# moire_v2_2.net
KiCad netlist of a schematic drawn in EAGLE
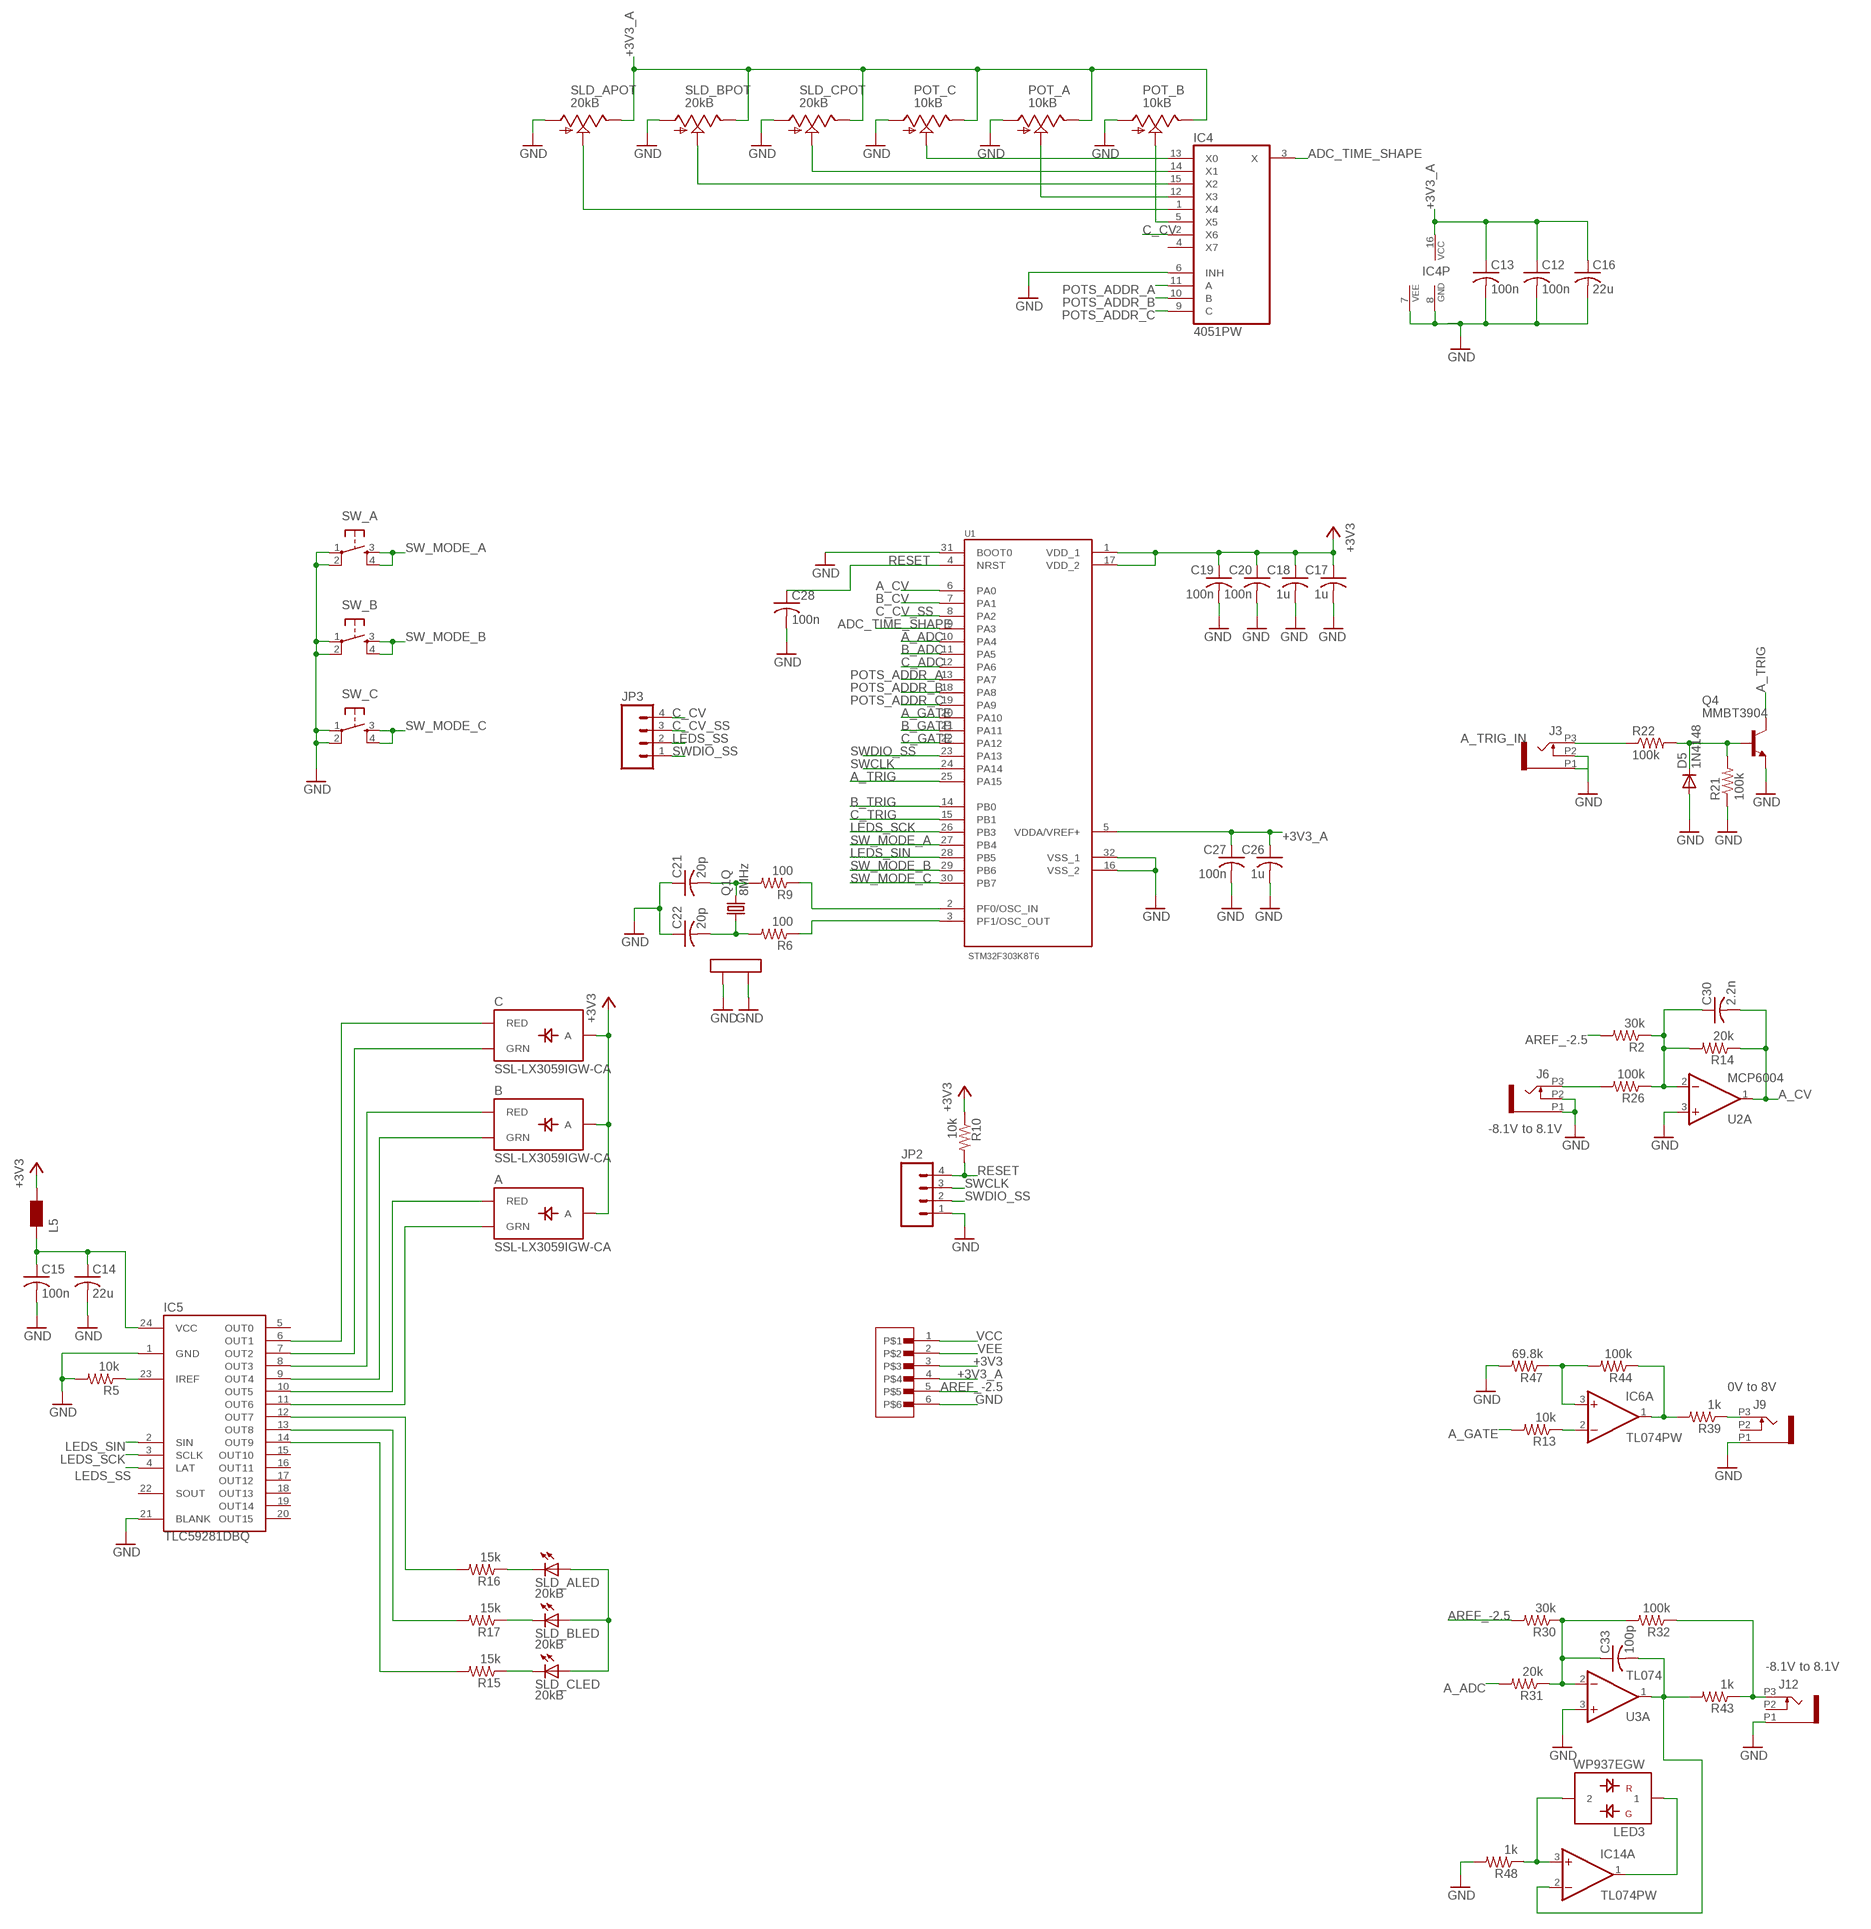
[diagram p0: schematic, sheet 1, part 1 of 2]
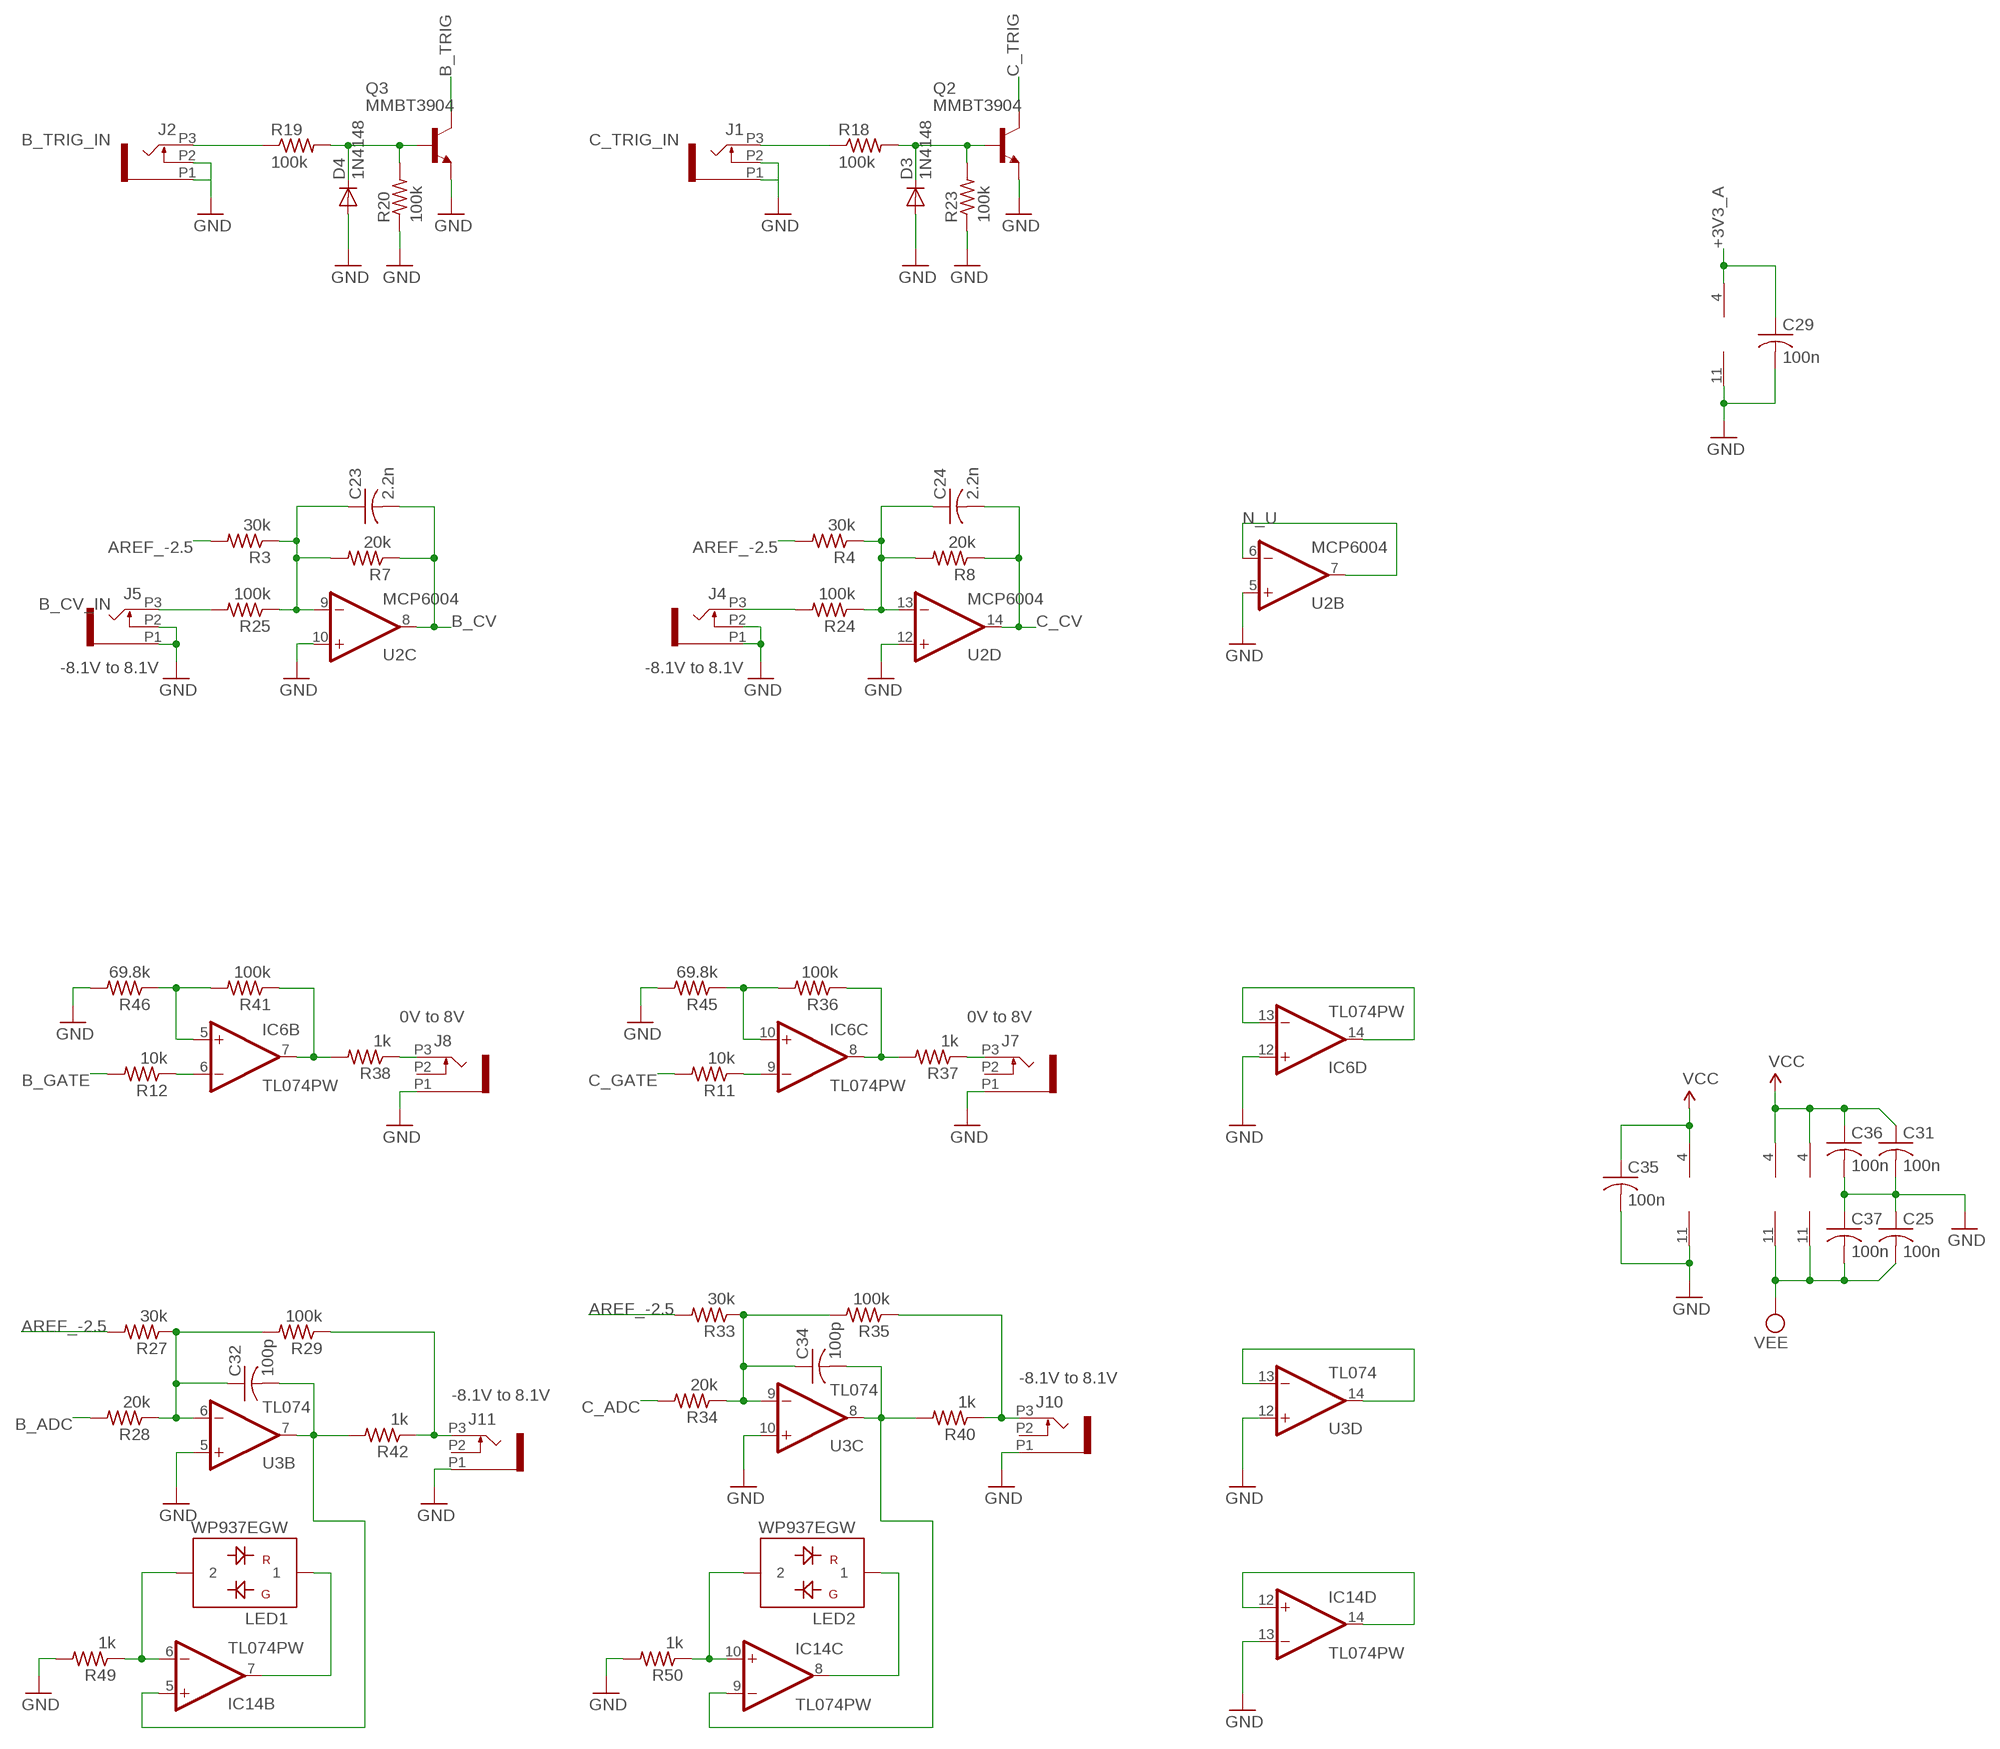
[diagram p1: schematic, sheet 1, part 2 of 2]
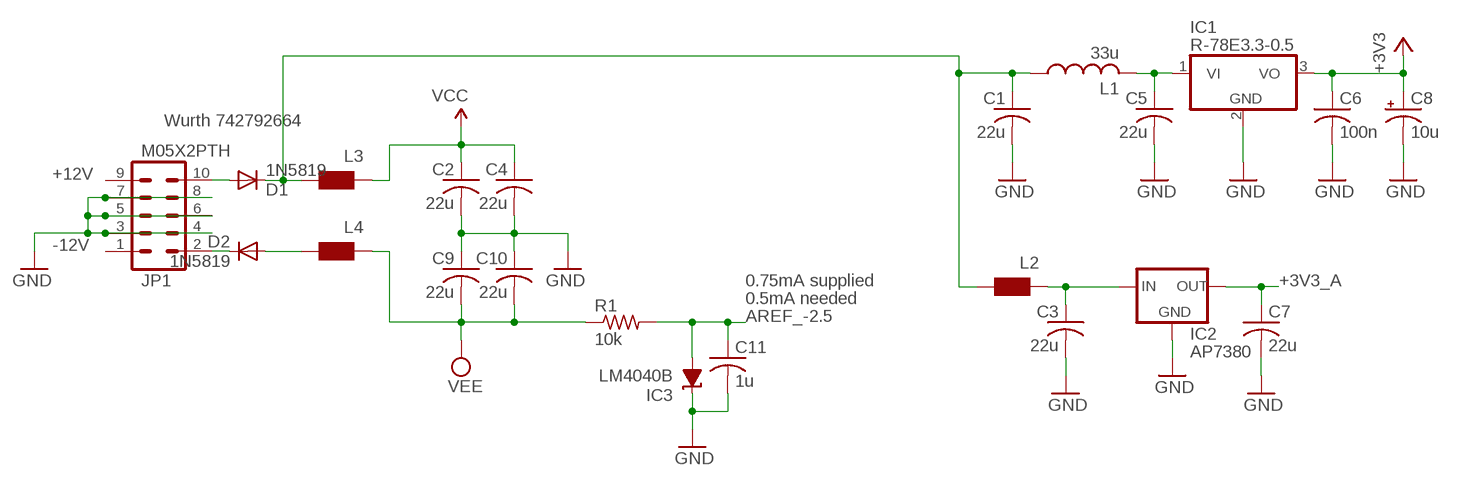
[diagram p2: schematic, sheet 2]

(export (version "E")
  (design (tool "Eeschema 10.0.6"))
  (components
    (comp (ref "A")
      (value "SSL-LX3059IGW-CA")
      (footprint "eagle-import:LED-BICOLOR-THROUGHHOLE-LUMEX")
      (libsource (lib "eagle-import") (part "LED-BICOLOR-THROUGHHOLE-CA"))
    )
    (comp (ref "B")
      (value "SSL-LX3059IGW-CA")
      (footprint "eagle-import:LED-BICOLOR-THROUGHHOLE-LUMEX")
      (libsource (lib "eagle-import") (part "LED-BICOLOR-THROUGHHOLE-CA"))
    )
    (comp (ref "C")
      (value "SSL-LX3059IGW-CA")
      (footprint "eagle-import:LED-BICOLOR-THROUGHHOLE-LUMEX")
      (libsource (lib "eagle-import") (part "LED-BICOLOR-THROUGHHOLE-CA"))
    )
    (comp (ref "C12")
      (value "100n")
      (footprint "eagle-import:RCL_C0603")
      (libsource (lib "eagle-import") (part "RCL_C-USC0603"))
    )
    (comp (ref "C13")
      (value "100n")
      (footprint "eagle-import:RCL_C0603")
      (libsource (lib "eagle-import") (part "RCL_C-USC0603"))
    )
    (comp (ref "C14")
      (value "22u")
      (footprint "eagle-import:RCL_C1206")
      (libsource (lib "eagle-import") (part "RCL_C-USC1206"))
    )
    (comp (ref "C15")
      (value "100n")
      (footprint "eagle-import:RCL_C0603")
      (libsource (lib "eagle-import") (part "RCL_C-USC0603"))
    )
    (comp (ref "C16")
      (value "22u")
      (footprint "eagle-import:RCL_C1206")
      (libsource (lib "eagle-import") (part "RCL_C-USC1206"))
    )
    (comp (ref "C17")
      (value "1u")
      (footprint "eagle-import:RCL_C0603")
      (libsource (lib "eagle-import") (part "RCL_C-USC0603"))
    )
    (comp (ref "C18")
      (value "1u")
      (footprint "eagle-import:RCL_C0603")
      (libsource (lib "eagle-import") (part "RCL_C-USC0603"))
    )
    (comp (ref "C19")
      (value "100n")
      (footprint "eagle-import:RCL_C0603")
      (libsource (lib "eagle-import") (part "RCL_C-USC0603"))
    )
    (comp (ref "C20")
      (value "100n")
      (footprint "eagle-import:RCL_C0603")
      (libsource (lib "eagle-import") (part "RCL_C-USC0603"))
    )
    (comp (ref "C21")
      (value "20p")
      (footprint "eagle-import:RCL_C0603")
      (libsource (lib "eagle-import") (part "RCL_C-USC0603"))
    )
    (comp (ref "C22")
      (value "20p")
      (footprint "eagle-import:RCL_C0603")
      (libsource (lib "eagle-import") (part "RCL_C-USC0603"))
    )
    (comp (ref "C23")
      (value "2.2n")
      (footprint "eagle-import:RCL_C0603")
      (libsource (lib "eagle-import") (part "RCL_C-USC0603"))
    )
    (comp (ref "C24")
      (value "2.2n")
      (footprint "eagle-import:RCL_C0603")
      (libsource (lib "eagle-import") (part "RCL_C-USC0603"))
    )
    (comp (ref "C25")
      (value "100n")
      (footprint "eagle-import:RCL_C0603")
      (libsource (lib "eagle-import") (part "RCL_C-USC0603"))
    )
    (comp (ref "C26")
      (value "1u")
      (footprint "eagle-import:RCL_C0603")
      (libsource (lib "eagle-import") (part "RCL_C-USC0603"))
    )
    (comp (ref "C27")
      (value "100n")
      (footprint "eagle-import:RCL_C0603")
      (libsource (lib "eagle-import") (part "RCL_C-USC0603"))
    )
    (comp (ref "C28")
      (value "100n")
      (footprint "eagle-import:RCL_C0603")
      (libsource (lib "eagle-import") (part "RCL_C-USC0603"))
    )
    (comp (ref "C29")
      (value "100n")
      (footprint "eagle-import:RCL_C0603")
      (libsource (lib "eagle-import") (part "RCL_C-USC0603"))
    )
    (comp (ref "C30")
      (value "2.2n")
      (footprint "eagle-import:RCL_C0603")
      (libsource (lib "eagle-import") (part "RCL_C-USC0603"))
    )
    (comp (ref "C31")
      (value "100n")
      (footprint "eagle-import:RCL_C0603")
      (libsource (lib "eagle-import") (part "RCL_C-USC0603"))
    )
    (comp (ref "C32")
      (value "100p")
      (footprint "eagle-import:RCL_C0603")
      (libsource (lib "eagle-import") (part "RCL_C-USC0603"))
    )
    (comp (ref "C33")
      (value "100p")
      (footprint "eagle-import:RCL_C0603")
      (libsource (lib "eagle-import") (part "RCL_C-USC0603"))
    )
    (comp (ref "C34")
      (value "100p")
      (footprint "eagle-import:RCL_C0603")
      (libsource (lib "eagle-import") (part "RCL_C-USC0603"))
    )
    (comp (ref "C35")
      (value "100n")
      (footprint "eagle-import:RCL_C0603")
      (libsource (lib "eagle-import") (part "RCL_C-USC0603"))
    )
    (comp (ref "C36")
      (value "100n")
      (footprint "eagle-import:RCL_C0603")
      (libsource (lib "eagle-import") (part "RCL_C-USC0603"))
    )
    (comp (ref "C37")
      (value "100n")
      (footprint "eagle-import:RCL_C0603")
      (libsource (lib "eagle-import") (part "RCL_C-USC0603"))
    )
    (comp (ref "D3")
      (value "1N4148")
      (footprint "eagle-import:DIODE_SOD523")
      (libsource (lib "eagle-import") (part "DIODE_DIODE-SOD523"))
    )
    (comp (ref "D4")
      (value "1N4148")
      (footprint "eagle-import:DIODE_SOD523")
      (libsource (lib "eagle-import") (part "DIODE_DIODE-SOD523"))
    )
    (comp (ref "D5")
      (value "1N4148")
      (footprint "eagle-import:DIODE_SOD523")
      (libsource (lib "eagle-import") (part "DIODE_DIODE-SOD523"))
    )
    (comp (ref "IC4")
      (value "4051PW")
      (footprint "eagle-import:TSSOP16_065")
      (libsource (lib "eagle-import") (part "4051PW"))
    )
    (comp (ref "IC5")
      (value "TLC59281DBQ")
      (footprint "eagle-import:TSSOP24_0635")
      (libsource (lib "eagle-import") (part "TLC59281DBQ"))
    )
    (comp (ref "IC6")
      (value "TL074PW")
      (footprint "eagle-import:TSSOP14_065")
      (libsource (lib "eagle-import") (part "og-linear_TL074PW"))
    )
    (comp (ref "IC14")
      (value "TL074PW")
      (footprint "eagle-import:TSSOP14_065")
      (libsource (lib "eagle-import") (part "TL074PW"))
    )
    (comp (ref "J1")
      (value "PJ301_THONKICONN6")
      (footprint "eagle-import:WQP_PJ_301M6")
      (libsource (lib "eagle-import") (part "PJ301_THONKICONN6"))
    )
    (comp (ref "J2")
      (value "PJ301_THONKICONN6")
      (footprint "eagle-import:WQP_PJ_301M6")
      (libsource (lib "eagle-import") (part "PJ301_THONKICONN6"))
    )
    (comp (ref "J3")
      (value "PJ301_THONKICONN6")
      (footprint "eagle-import:WQP_PJ_301M6")
      (libsource (lib "eagle-import") (part "PJ301_THONKICONN6"))
    )
    (comp (ref "J4")
      (value "PJ301_THONKICONN6")
      (footprint "eagle-import:WQP_PJ_301M6")
      (libsource (lib "eagle-import") (part "PJ301_THONKICONN6"))
    )
    (comp (ref "J5")
      (value "PJ301_THONKICONN6")
      (footprint "eagle-import:WQP_PJ_301M6")
      (libsource (lib "eagle-import") (part "PJ301_THONKICONN6"))
    )
    (comp (ref "J6")
      (value "PJ301_THONKICONN6")
      (footprint "eagle-import:WQP_PJ_301M6")
      (libsource (lib "eagle-import") (part "PJ301_THONKICONN6"))
    )
    (comp (ref "J7")
      (value "PJ301_THONKICONN6")
      (footprint "eagle-import:WQP_PJ_301M6")
      (libsource (lib "eagle-import") (part "PJ301_THONKICONN6"))
    )
    (comp (ref "J8")
      (value "PJ301_THONKICONN6")
      (footprint "eagle-import:WQP_PJ_301M6")
      (libsource (lib "eagle-import") (part "PJ301_THONKICONN6"))
    )
    (comp (ref "J9")
      (value "PJ301_THONKICONN6")
      (footprint "eagle-import:WQP_PJ_301M6")
      (libsource (lib "eagle-import") (part "PJ301_THONKICONN6"))
    )
    (comp (ref "J10")
      (value "PJ301_THONKICONN6")
      (footprint "eagle-import:WQP_PJ_301M6")
      (libsource (lib "eagle-import") (part "PJ301_THONKICONN6"))
    )
    (comp (ref "J11")
      (value "PJ301_THONKICONN6")
      (footprint "eagle-import:WQP_PJ_301M6")
      (libsource (lib "eagle-import") (part "PJ301_THONKICONN6"))
    )
    (comp (ref "J12")
      (value "PJ301_THONKICONN6")
      (footprint "eagle-import:WQP_PJ_301M6")
      (libsource (lib "eagle-import") (part "PJ301_THONKICONN6"))
    )
    (comp (ref "JP2")
      (value "M04PTH")
      (footprint "eagle-import:1X04")
      (libsource (lib "eagle-import") (part "M04PTH"))
    )
    (comp (ref "JP3")
      (value "M04PTH")
      (footprint "eagle-import:1X04")
      (libsource (lib "eagle-import") (part "M04PTH"))
    )
    (comp (ref "L5")
      (value "WE-CBF_0603")
      (footprint "eagle-import:0603")
      (libsource (lib "eagle-import") (part "WE-CBF_0603"))
    )
    (comp (ref "LED1")
      (value "WP937EGW")
      (footprint "eagle-import:LED3MM")
      (libsource (lib "eagle-import") (part "LED-BICOLOR-SHARED-THROUGHHOLE"))
    )
    (comp (ref "LED2")
      (value "WP937EGW")
      (footprint "eagle-import:LED3MM")
      (libsource (lib "eagle-import") (part "LED-BICOLOR-SHARED-THROUGHHOLE"))
    )
    (comp (ref "LED3")
      (value "WP937EGW")
      (footprint "eagle-import:LED3MM")
      (libsource (lib "eagle-import") (part "LED-BICOLOR-SHARED-THROUGHHOLE"))
    )
    (comp (ref "POT_A")
      (value "10kB")
      (footprint "eagle-import:ALPS_POT_VERTICAL")
      (libsource (lib "eagle-import") (part "POT_USVERTICAL"))
    )
    (comp (ref "POT_B")
      (value "10kB")
      (footprint "eagle-import:ALPS_POT_VERTICAL")
      (libsource (lib "eagle-import") (part "POT_USVERTICAL"))
    )
    (comp (ref "POT_C")
      (value "10kB")
      (footprint "eagle-import:ALPS_POT_VERTICAL")
      (libsource (lib "eagle-import") (part "POT_USVERTICAL"))
    )
    (comp (ref "Q1")
      (value "8MHz")
      (footprint "eagle-import:CTS406")
      (libsource (lib "eagle-import") (part "CRYSTAL"))
    )
    (comp (ref "Q2")
      (value "MMBT3904")
      (footprint "eagle-import:SOT23-BEC")
      (libsource (lib "eagle-import") (part "-NPN-SOT23-BECMMBT3904LT1"))
    )
    (comp (ref "Q3")
      (value "MMBT3904")
      (footprint "eagle-import:SOT23-BEC")
      (libsource (lib "eagle-import") (part "-NPN-SOT23-BECMMBT3904LT1"))
    )
    (comp (ref "Q4")
      (value "MMBT3904")
      (footprint "eagle-import:SOT23-BEC")
      (libsource (lib "eagle-import") (part "-NPN-SOT23-BECMMBT3904LT1"))
    )
    (comp (ref "R2")
      (value "30k")
      (footprint "eagle-import:RCL_R0603")
      (libsource (lib "eagle-import") (part "RCL_R-US_R0603"))
    )
    (comp (ref "R3")
      (value "30k")
      (footprint "eagle-import:RCL_R0603")
      (libsource (lib "eagle-import") (part "RCL_R-US_R0603"))
    )
    (comp (ref "R4")
      (value "30k")
      (footprint "eagle-import:RCL_R0603")
      (libsource (lib "eagle-import") (part "RCL_R-US_R0603"))
    )
    (comp (ref "R5")
      (value "10k")
      (footprint "eagle-import:RCL_R0603")
      (libsource (lib "eagle-import") (part "RCL_R-US_R0603"))
    )
    (comp (ref "R6")
      (value "100")
      (footprint "eagle-import:RCL_R0603")
      (libsource (lib "eagle-import") (part "RCL_R-US_R0603"))
    )
    (comp (ref "R7")
      (value "20k")
      (footprint "eagle-import:RCL_R0603")
      (libsource (lib "eagle-import") (part "RCL_R-US_R0603"))
    )
    (comp (ref "R8")
      (value "20k")
      (footprint "eagle-import:RCL_R0603")
      (libsource (lib "eagle-import") (part "RCL_R-US_R0603"))
    )
    (comp (ref "R9")
      (value "100")
      (footprint "eagle-import:RCL_R0603")
      (libsource (lib "eagle-import") (part "RCL_R-US_R0603"))
    )
    (comp (ref "R10")
      (value "10k")
      (footprint "eagle-import:RCL_R0603")
      (libsource (lib "eagle-import") (part "RCL_R-US_R0603"))
    )
    (comp (ref "R11")
      (value "10k")
      (footprint "eagle-import:RCL_R0603")
      (libsource (lib "eagle-import") (part "RCL_R-US_R0603"))
    )
    (comp (ref "R12")
      (value "10k")
      (footprint "eagle-import:RCL_R0603")
      (libsource (lib "eagle-import") (part "RCL_R-US_R0603"))
    )
    (comp (ref "R13")
      (value "10k")
      (footprint "eagle-import:RCL_R0603")
      (libsource (lib "eagle-import") (part "RCL_R-US_R0603"))
    )
    (comp (ref "R14")
      (value "20k")
      (footprint "eagle-import:RCL_R0603")
      (libsource (lib "eagle-import") (part "RCL_R-US_R0603"))
    )
    (comp (ref "R15")
      (value "15k")
      (footprint "eagle-import:RCL_R0603")
      (libsource (lib "eagle-import") (part "RCL_R-US_R0603"))
    )
    (comp (ref "R16")
      (value "15k")
      (footprint "eagle-import:RCL_R0603")
      (libsource (lib "eagle-import") (part "RCL_R-US_R0603"))
    )
    (comp (ref "R17")
      (value "15k")
      (footprint "eagle-import:RCL_R0603")
      (libsource (lib "eagle-import") (part "RCL_R-US_R0603"))
    )
    (comp (ref "R18")
      (value "100k")
      (footprint "eagle-import:RCL_R0603")
      (libsource (lib "eagle-import") (part "RCL_R-US_R0603"))
    )
    (comp (ref "R19")
      (value "100k")
      (footprint "eagle-import:RCL_R0603")
      (libsource (lib "eagle-import") (part "RCL_R-US_R0603"))
    )
    (comp (ref "R20")
      (value "100k")
      (footprint "eagle-import:RCL_R0603")
      (libsource (lib "eagle-import") (part "RCL_R-US_R0603"))
    )
    (comp (ref "R21")
      (value "100k")
      (footprint "eagle-import:RCL_R0603")
      (libsource (lib "eagle-import") (part "RCL_R-US_R0603"))
    )
    (comp (ref "R22")
      (value "100k")
      (footprint "eagle-import:RCL_R0603")
      (libsource (lib "eagle-import") (part "RCL_R-US_R0603"))
    )
    (comp (ref "R23")
      (value "100k")
      (footprint "eagle-import:RCL_R0603")
      (libsource (lib "eagle-import") (part "RCL_R-US_R0603"))
    )
    (comp (ref "R24")
      (value "100k")
      (footprint "eagle-import:RCL_R0603")
      (libsource (lib "eagle-import") (part "RCL_R-US_R0603"))
    )
    (comp (ref "R25")
      (value "100k")
      (footprint "eagle-import:RCL_R0603")
      (libsource (lib "eagle-import") (part "RCL_R-US_R0603"))
    )
    (comp (ref "R26")
      (value "100k")
      (footprint "eagle-import:RCL_R0603")
      (libsource (lib "eagle-import") (part "RCL_R-US_R0603"))
    )
    (comp (ref "R27")
      (value "30k")
      (footprint "eagle-import:RCL_R0603")
      (libsource (lib "eagle-import") (part "RCL_R-US_R0603"))
    )
    (comp (ref "R28")
      (value "20k")
      (footprint "eagle-import:RCL_R0603")
      (libsource (lib "eagle-import") (part "RCL_R-US_R0603"))
    )
    (comp (ref "R29")
      (value "100k")
      (footprint "eagle-import:RCL_R0603")
      (libsource (lib "eagle-import") (part "RCL_R-US_R0603"))
    )
    (comp (ref "R30")
      (value "30k")
      (footprint "eagle-import:RCL_R0603")
      (libsource (lib "eagle-import") (part "RCL_R-US_R0603"))
    )
    (comp (ref "R31")
      (value "20k")
      (footprint "eagle-import:RCL_R0603")
      (libsource (lib "eagle-import") (part "RCL_R-US_R0603"))
    )
    (comp (ref "R32")
      (value "100k")
      (footprint "eagle-import:RCL_R0603")
      (libsource (lib "eagle-import") (part "RCL_R-US_R0603"))
    )
    (comp (ref "R33")
      (value "30k")
      (footprint "eagle-import:RCL_R0603")
      (libsource (lib "eagle-import") (part "RCL_R-US_R0603"))
    )
    (comp (ref "R34")
      (value "20k")
      (footprint "eagle-import:RCL_R0603")
      (libsource (lib "eagle-import") (part "RCL_R-US_R0603"))
    )
    (comp (ref "R35")
      (value "100k")
      (footprint "eagle-import:RCL_R0603")
      (libsource (lib "eagle-import") (part "RCL_R-US_R0603"))
    )
    (comp (ref "R36")
      (value "100k")
      (footprint "eagle-import:RCL_R0603")
      (libsource (lib "eagle-import") (part "RCL_R-US_R0603"))
    )
    (comp (ref "R37")
      (value "1k")
      (footprint "eagle-import:RCL_R0603")
      (libsource (lib "eagle-import") (part "RCL_R-US_R0603"))
    )
    (comp (ref "R38")
      (value "1k")
      (footprint "eagle-import:RCL_R0603")
      (libsource (lib "eagle-import") (part "RCL_R-US_R0603"))
    )
    (comp (ref "R39")
      (value "1k")
      (footprint "eagle-import:RCL_R0603")
      (libsource (lib "eagle-import") (part "RCL_R-US_R0603"))
    )
    (comp (ref "R40")
      (value "1k")
      (footprint "eagle-import:RCL_R0603")
      (libsource (lib "eagle-import") (part "RCL_R-US_R0603"))
    )
    (comp (ref "R41")
      (value "100k")
      (footprint "eagle-import:RCL_R0603")
      (libsource (lib "eagle-import") (part "RCL_R-US_R0603"))
    )
    (comp (ref "R42")
      (value "1k")
      (footprint "eagle-import:RCL_R0603")
      (libsource (lib "eagle-import") (part "RCL_R-US_R0603"))
    )
    (comp (ref "R43")
      (value "1k")
      (footprint "eagle-import:RCL_R0603")
      (libsource (lib "eagle-import") (part "RCL_R-US_R0603"))
    )
    (comp (ref "R44")
      (value "100k")
      (footprint "eagle-import:RCL_R0603")
      (libsource (lib "eagle-import") (part "RCL_R-US_R0603"))
    )
    (comp (ref "R45")
      (value "69.8k")
      (footprint "eagle-import:RCL_R0603")
      (libsource (lib "eagle-import") (part "RCL_R-US_R0603"))
    )
    (comp (ref "R46")
      (value "69.8k")
      (footprint "eagle-import:RCL_R0603")
      (libsource (lib "eagle-import") (part "RCL_R-US_R0603"))
    )
    (comp (ref "R47")
      (value "69.8k")
      (footprint "eagle-import:RCL_R0603")
      (libsource (lib "eagle-import") (part "RCL_R-US_R0603"))
    )
    (comp (ref "R48")
      (value "1k")
      (footprint "eagle-import:RCL_R0603")
      (libsource (lib "eagle-import") (part "RCL_R-US_R0603"))
    )
    (comp (ref "R49")
      (value "1k")
      (footprint "eagle-import:RCL_R0603")
      (libsource (lib "eagle-import") (part "RCL_R-US_R0603"))
    )
    (comp (ref "R50")
      (value "1k")
      (footprint "eagle-import:RCL_R0603")
      (libsource (lib "eagle-import") (part "RCL_R-US_R0603"))
    )
    (comp (ref "SLD_A")
      (value "20kB")
      (footprint "eagle-import:BOURNS_SLIDER")
      (libsource (lib "eagle-import") (part "BOURNS_SLIDER"))
    )
    (comp (ref "SLD_B")
      (value "20kB")
      (footprint "eagle-import:BOURNS_SLIDER")
      (libsource (lib "eagle-import") (part "BOURNS_SLIDER"))
    )
    (comp (ref "SLD_C")
      (value "20kB")
      (footprint "eagle-import:BOURNS_SLIDER")
      (libsource (lib "eagle-import") (part "BOURNS_SLIDER"))
    )
    (comp (ref "SW_A")
      (value "TAC_SWITCHPTH")
      (footprint "eagle-import:TACTILE-PTH")
      (libsource (lib "eagle-import") (part "TAC_SWITCHPTH"))
    )
    (comp (ref "SW_B")
      (value "TAC_SWITCHPTH")
      (footprint "eagle-import:TACTILE-PTH")
      (libsource (lib "eagle-import") (part "TAC_SWITCHPTH"))
    )
    (comp (ref "SW_C")
      (value "TAC_SWITCHPTH")
      (footprint "eagle-import:TACTILE-PTH")
      (libsource (lib "eagle-import") (part "TAC_SWITCHPTH"))
    )
    (comp (ref "U$1")
      (value "1X6-SMD-TESTPAD")
      (footprint "eagle-import:6X1-SMD-TESTPAD")
      (libsource (lib "eagle-import") (part "1X6-SMD-TESTPAD"))
    )
    (comp (ref "U1")
      (value "STM32F303K8T6")
      (footprint "eagle-import:QFP80P900X900X160-32N")
      (fields (field (name "MF") "STMicroelectronics"))
      (libsource (lib "eagle-import") (part "STM32F303K8T6"))
    )
    (comp (ref "U2")
      (value "MCP6004")
      (footprint "eagle-import:SO14")
      (libsource (lib "eagle-import") (part "MCP6004_SMD"))
    )
    (comp (ref "U3")
      (value "TL074")
      (footprint "eagle-import:SO14")
      (libsource (lib "eagle-import") (part "TL074_SMD"))
    )
    (comp (ref "C1")
      (value "22u")
      (footprint "eagle-import:RCL_C1206")
      (libsource (lib "eagle-import") (part "RCL_C-USC1206"))
    )
    (comp (ref "C2")
      (value "22u")
      (footprint "eagle-import:RCL_C1206")
      (libsource (lib "eagle-import") (part "RCL_C-USC1206"))
    )
    (comp (ref "C3")
      (value "22u")
      (footprint "eagle-import:RCL_C1206")
      (libsource (lib "eagle-import") (part "RCL_C-USC1206"))
    )
    (comp (ref "C4")
      (value "22u")
      (footprint "eagle-import:RCL_C1206")
      (libsource (lib "eagle-import") (part "RCL_C-USC1206"))
    )
    (comp (ref "C5")
      (value "22u")
      (footprint "eagle-import:RCL_C1206")
      (libsource (lib "eagle-import") (part "RCL_C-USC1206"))
    )
    (comp (ref "C6")
      (value "100n")
      (footprint "eagle-import:RCL_C0603")
      (libsource (lib "eagle-import") (part "RCL_C-USC0603"))
    )
    (comp (ref "C7")
      (value "22u")
      (footprint "eagle-import:RCL_C1206")
      (libsource (lib "eagle-import") (part "RCL_C-USC1206"))
    )
    (comp (ref "C8")
      (value "10u")
      (footprint "eagle-import:RCL_PANASONIC_A")
      (libsource (lib "eagle-import") (part "RCL_CPOL-USA"))
    )
    (comp (ref "C9")
      (value "22u")
      (footprint "eagle-import:RCL_C1206")
      (libsource (lib "eagle-import") (part "RCL_C-USC1206"))
    )
    (comp (ref "C10")
      (value "22u")
      (footprint "eagle-import:RCL_C1206")
      (libsource (lib "eagle-import") (part "RCL_C-USC1206"))
    )
    (comp (ref "C11")
      (value "1u")
      (footprint "eagle-import:RCL_C0603")
      (libsource (lib "eagle-import") (part "RCL_C-USC0603"))
    )
    (comp (ref "D1")
      (value "1N5819")
      (footprint "eagle-import:DIODE_SOD123")
      (libsource (lib "eagle-import") (part "DIODE_DIODE-SOD123"))
    )
    (comp (ref "D2")
      (value "1N5819")
      (footprint "eagle-import:DIODE_SOD123")
      (libsource (lib "eagle-import") (part "DIODE_DIODE-SOD123"))
    )
    (comp (ref "IC1")
      (value "R-78E3.3-0.5")
      (footprint "eagle-import:WE78")
      (libsource (lib "eagle-import") (part "WE173950378"))
    )
    (comp (ref "IC2")
      (value "AP7380")
      (footprint "eagle-import:SOT89")
      (libsource (lib "eagle-import") (part "AP7380"))
    )
    (comp (ref "IC3")
      (value "LM4040B")
      (footprint "eagle-import:DBZ_R-PDSO-G3")
      (libsource (lib "eagle-import") (part "LM4041DBZB12"))
    )
    (comp (ref "JP1")
      (value "M05X2PTH")
      (footprint "eagle-import:2X5-PTH")
      (libsource (lib "eagle-import") (part "M05X2PTH"))
    )
    (comp (ref "L1")
      (value "33u")
      (footprint "eagle-import:L2012C")
      (libsource (lib "eagle-import") (part "L-USL2012C"))
    )
    (comp (ref "L2")
      (value "WE-CBF_0603")
      (footprint "eagle-import:0603")
      (libsource (lib "eagle-import") (part "WE-CBF_0603"))
    )
    (comp (ref "L3")
      (value "WE-CBF_0603")
      (footprint "eagle-import:0603")
      (libsource (lib "eagle-import") (part "WE-CBF_0603"))
    )
    (comp (ref "L4")
      (value "WE-CBF_0603")
      (footprint "eagle-import:0603")
      (libsource (lib "eagle-import") (part "WE-CBF_0603"))
    )
    (comp (ref "R1")
      (value "10k")
      (footprint "eagle-import:RCL_R0603")
      (libsource (lib "eagle-import") (part "RCL_R-US_R0603"))
    )
  )
  (nets
    (net (code "1") (name "+3V3") (class "Default")
      (node (ref "A") (pin "A") (pinfunction "A_A") (pintype "bidirectional"))
      (node (ref "B") (pin "A") (pinfunction "A_A") (pintype "bidirectional"))
      (node (ref "C") (pin "A") (pinfunction "A_A") (pintype "bidirectional"))
      (node (ref "C17") (pin "1") (pinfunction "1_1") (pintype "passive"))
      (node (ref "C18") (pin "1") (pinfunction "1_1") (pintype "passive"))
      (node (ref "C19") (pin "1") (pinfunction "1_1") (pintype "passive"))
      (node (ref "C20") (pin "1") (pinfunction "1_1") (pintype "passive"))
      (node (ref "C6") (pin "1") (pinfunction "1_1") (pintype "passive"))
      (node (ref "C8") (pin "+") (pinfunction "+_+") (pintype "passive"))
      (node (ref "IC1") (pin "3") (pinfunction "VO_3") (pintype "passive"))
      (node (ref "L5") (pin "2") (pinfunction "2_2") (pintype "passive"))
      (node (ref "R10") (pin "1") (pinfunction "1_1") (pintype "passive"))
      (node (ref "U$1") (pin "3") (pinfunction "P$3_3") (pintype "bidirectional"))
      (node (ref "U1") (pin "1") (pinfunction "VDD_1_1") (pintype "power_in"))
      (node (ref "U1") (pin "17") (pinfunction "VDD_2_17") (pintype "power_in"))
    )
    (net (code "2") (name "+3V3_A") (class "Default")
      (node (ref "C12") (pin "1") (pinfunction "1_1") (pintype "passive"))
      (node (ref "C13") (pin "1") (pinfunction "1_1") (pintype "passive"))
      (node (ref "C16") (pin "1") (pinfunction "1_1") (pintype "passive"))
      (node (ref "C26") (pin "1") (pinfunction "1_1") (pintype "passive"))
      (node (ref "C27") (pin "1") (pinfunction "1_1") (pintype "passive"))
      (node (ref "C29") (pin "1") (pinfunction "1_1") (pintype "passive"))
      (node (ref "C7") (pin "1") (pinfunction "1_1") (pintype "passive"))
      (node (ref "IC2") (pin "3") (pinfunction "OUT_3") (pintype "passive"))
      (node (ref "IC4") (pin "16") (pinfunction "VCC_16") (pintype "power_in"))
      (node (ref "POT_A") (pin "P$1") (pinfunction "E_P$1") (pintype "passive"))
      (node (ref "POT_B") (pin "P$1") (pinfunction "E_P$1") (pintype "passive"))
      (node (ref "POT_C") (pin "P$1") (pinfunction "E_P$1") (pintype "passive"))
      (node (ref "SLD_A") (pin "3") (pinfunction "E_3") (pintype "passive"))
      (node (ref "SLD_B") (pin "3") (pinfunction "E_3") (pintype "passive"))
      (node (ref "SLD_C") (pin "3") (pinfunction "E_3") (pintype "passive"))
      (node (ref "U$1") (pin "4") (pinfunction "P$4_4") (pintype "bidirectional"))
      (node (ref "U1") (pin "5") (pinfunction "VDDA/VREF+_5") (pintype "power_in"))
      (node (ref "U2") (pin "4") (pinfunction "V+_4") (pintype "power_in"))
    )
    (net (code "3") (name "+12V") (class "Default")
      (node (ref "D1") (pin "A") (pinfunction "A_A") (pintype "passive"))
      (node (ref "JP1") (pin "10") (pinfunction "10_10") (pintype "passive"))
      (node (ref "JP1") (pin "9") (pinfunction "9_9") (pintype "passive"))
    )
    (net (code "4") (name "-12V") (class "Default")
      (node (ref "D2") (pin "C") (pinfunction "C_C") (pintype "passive"))
      (node (ref "JP1") (pin "1") (pinfunction "1_1") (pintype "passive"))
      (node (ref "JP1") (pin "2") (pinfunction "2_2") (pintype "passive"))
    )
    (net (code "5") (name "ADC_TIME_SHAPE") (class "Default")
      (node (ref "IC4") (pin "3") (pinfunction "X_3") (pintype "bidirectional"))
      (node (ref "U1") (pin "9") (pinfunction "PA3_9") (pintype "bidirectional"))
    )
    (net (code "6") (name "AREF_-2.5") (class "Default")
      (node (ref "C11") (pin "1") (pinfunction "1_1") (pintype "passive"))
      (node (ref "IC3") (pin "2") (pinfunction "A_2") (pintype "passive"))
      (node (ref "R1") (pin "2") (pinfunction "2_2") (pintype "passive"))
      (node (ref "R2") (pin "2") (pinfunction "2_2") (pintype "passive"))
      (node (ref "R27") (pin "2") (pinfunction "2_2") (pintype "passive"))
      (node (ref "R3") (pin "2") (pinfunction "2_2") (pintype "passive"))
      (node (ref "R30") (pin "2") (pinfunction "2_2") (pintype "passive"))
      (node (ref "R33") (pin "2") (pinfunction "2_2") (pintype "passive"))
      (node (ref "R4") (pin "2") (pinfunction "2_2") (pintype "passive"))
      (node (ref "U$1") (pin "5") (pinfunction "P$5_5") (pintype "bidirectional"))
    )
    (net (code "7") (name "A_ADC") (class "Default")
      (node (ref "R31") (pin "2") (pinfunction "2_2") (pintype "passive"))
      (node (ref "U1") (pin "10") (pinfunction "PA4_10") (pintype "bidirectional"))
    )
    (net (code "8") (name "A_CV") (class "Default")
      (node (ref "C30") (pin "2") (pinfunction "2_2") (pintype "passive"))
      (node (ref "R14") (pin "1") (pinfunction "1_1") (pintype "passive"))
      (node (ref "U1") (pin "6") (pinfunction "PA0_6") (pintype "bidirectional"))
      (node (ref "U2") (pin "1") (pinfunction "OUT_1") (pintype "output"))
    )
    (net (code "9") (name "A_GATE") (class "Default")
      (node (ref "R13") (pin "2") (pinfunction "2_2") (pintype "passive"))
      (node (ref "U1") (pin "20") (pinfunction "PA10_20") (pintype "bidirectional"))
    )
    (net (code "10") (name "A_TRIG") (class "Default")
      (node (ref "Q4") (pin "C") (pinfunction "C_C") (pintype "passive"))
      (node (ref "U1") (pin "25") (pinfunction "PA15_25") (pintype "bidirectional"))
    )
    (net (code "11") (name "A_TRIG_IN") (class "Default")
      (node (ref "J3") (pin "P3") (pinfunction "3_P3") (pintype "passive"))
      (node (ref "R22") (pin "1") (pinfunction "1_1") (pintype "passive"))
    )
    (net (code "12") (name "B_ADC") (class "Default")
      (node (ref "R28") (pin "2") (pinfunction "2_2") (pintype "passive"))
      (node (ref "U1") (pin "11") (pinfunction "PA5_11") (pintype "bidirectional"))
    )
    (net (code "13") (name "B_CV") (class "Default")
      (node (ref "C23") (pin "2") (pinfunction "2_2") (pintype "passive"))
      (node (ref "R7") (pin "1") (pinfunction "1_1") (pintype "passive"))
      (node (ref "U1") (pin "7") (pinfunction "PA1_7") (pintype "bidirectional"))
      (node (ref "U2") (pin "8") (pinfunction "OUT_8") (pintype "output"))
    )
    (net (code "14") (name "B_CV_IN") (class "Default")
      (node (ref "J5") (pin "P3") (pinfunction "3_P3") (pintype "passive"))
      (node (ref "R25") (pin "2") (pinfunction "2_2") (pintype "passive"))
    )
    (net (code "15") (name "B_GATE") (class "Default")
      (node (ref "R12") (pin "2") (pinfunction "2_2") (pintype "passive"))
      (node (ref "U1") (pin "21") (pinfunction "PA11_21") (pintype "bidirectional"))
    )
    (net (code "16") (name "B_TRIG") (class "Default")
      (node (ref "Q3") (pin "C") (pinfunction "C_C") (pintype "passive"))
      (node (ref "U1") (pin "14") (pinfunction "PB0_14") (pintype "bidirectional"))
    )
    (net (code "17") (name "B_TRIG_IN") (class "Default")
      (node (ref "J2") (pin "P3") (pinfunction "3_P3") (pintype "passive"))
      (node (ref "R19") (pin "1") (pinfunction "1_1") (pintype "passive"))
    )
    (net (code "18") (name "C_ADC") (class "Default")
      (node (ref "R34") (pin "2") (pinfunction "2_2") (pintype "passive"))
      (node (ref "U1") (pin "12") (pinfunction "PA6_12") (pintype "bidirectional"))
    )
    (net (code "19") (name "C_CV") (class "Default")
      (node (ref "C24") (pin "2") (pinfunction "2_2") (pintype "passive"))
      (node (ref "IC4") (pin "2") (pinfunction "X6_2") (pintype "bidirectional"))
      (node (ref "JP3") (pin "4") (pinfunction "4_4") (pintype "passive"))
      (node (ref "R8") (pin "1") (pinfunction "1_1") (pintype "passive"))
      (node (ref "U2") (pin "14") (pinfunction "OUT_14") (pintype "output"))
    )
    (net (code "20") (name "C_CV_SS") (class "Default")
      (node (ref "JP3") (pin "3") (pinfunction "3_3") (pintype "passive"))
      (node (ref "U1") (pin "8") (pinfunction "PA2_8") (pintype "bidirectional"))
    )
    (net (code "21") (name "C_GATE") (class "Default")
      (node (ref "R11") (pin "2") (pinfunction "2_2") (pintype "passive"))
      (node (ref "U1") (pin "22") (pinfunction "PA12_22") (pintype "bidirectional"))
    )
    (net (code "22") (name "C_TRIG") (class "Default")
      (node (ref "Q2") (pin "C") (pinfunction "C_C") (pintype "passive"))
      (node (ref "U1") (pin "15") (pinfunction "PB1_15") (pintype "bidirectional"))
    )
    (net (code "23") (name "C_TRIG_IN") (class "Default")
      (node (ref "J1") (pin "P3") (pinfunction "3_P3") (pintype "passive"))
      (node (ref "R18") (pin "1") (pinfunction "1_1") (pintype "passive"))
    )
    (net (code "24") (name "GND") (class "Default")
      (node (ref "C1") (pin "2") (pinfunction "2_2") (pintype "passive"))
      (node (ref "C10") (pin "1") (pinfunction "1_1") (pintype "passive"))
      (node (ref "C11") (pin "2") (pinfunction "2_2") (pintype "passive"))
      (node (ref "C12") (pin "2") (pinfunction "2_2") (pintype "passive"))
      (node (ref "C13") (pin "2") (pinfunction "2_2") (pintype "passive"))
      (node (ref "C14") (pin "2") (pinfunction "2_2") (pintype "passive"))
      (node (ref "C15") (pin "2") (pinfunction "2_2") (pintype "passive"))
      (node (ref "C16") (pin "2") (pinfunction "2_2") (pintype "passive"))
      (node (ref "C17") (pin "2") (pinfunction "2_2") (pintype "passive"))
      (node (ref "C18") (pin "2") (pinfunction "2_2") (pintype "passive"))
      (node (ref "C19") (pin "2") (pinfunction "2_2") (pintype "passive"))
      (node (ref "C2") (pin "2") (pinfunction "2_2") (pintype "passive"))
      (node (ref "C20") (pin "2") (pinfunction "2_2") (pintype "passive"))
      (node (ref "C21") (pin "1") (pinfunction "1_1") (pintype "passive"))
      (node (ref "C22") (pin "1") (pinfunction "1_1") (pintype "passive"))
      (node (ref "C25") (pin "1") (pinfunction "1_1") (pintype "passive"))
      (node (ref "C26") (pin "2") (pinfunction "2_2") (pintype "passive"))
      (node (ref "C27") (pin "2") (pinfunction "2_2") (pintype "passive"))
      (node (ref "C28") (pin "2") (pinfunction "2_2") (pintype "passive"))
      (node (ref "C29") (pin "2") (pinfunction "2_2") (pintype "passive"))
      (node (ref "C3") (pin "2") (pinfunction "2_2") (pintype "passive"))
      (node (ref "C31") (pin "2") (pinfunction "2_2") (pintype "passive"))
      (node (ref "C35") (pin "2") (pinfunction "2_2") (pintype "passive"))
      (node (ref "C36") (pin "2") (pinfunction "2_2") (pintype "passive"))
      (node (ref "C37") (pin "1") (pinfunction "1_1") (pintype "passive"))
      (node (ref "C4") (pin "2") (pinfunction "2_2") (pintype "passive"))
      (node (ref "C5") (pin "2") (pinfunction "2_2") (pintype "passive"))
      (node (ref "C6") (pin "2") (pinfunction "2_2") (pintype "passive"))
      (node (ref "C7") (pin "2") (pinfunction "2_2") (pintype "passive"))
      (node (ref "C8") (pin "-") (pinfunction "-_-") (pintype "passive"))
      (node (ref "C9") (pin "1") (pinfunction "1_1") (pintype "passive"))
      (node (ref "D3") (pin "A") (pinfunction "A_A") (pintype "passive"))
      (node (ref "D4") (pin "A") (pinfunction "A_A") (pintype "passive"))
      (node (ref "D5") (pin "A") (pinfunction "A_A") (pintype "passive"))
      (node (ref "IC1") (pin "2") (pinfunction "GND_2") (pintype "passive"))
      (node (ref "IC14") (pin "13") (pinfunction "-IN_13") (pintype "input"))
      (node (ref "IC2") (pin "1") (pinfunction "GND_1") (pintype "input"))
      (node (ref "IC3") (pin "1") (pinfunction "C_1") (pintype "passive"))
      (node (ref "IC4") (pin "6") (pinfunction "INH_6") (pintype "input"))
      (node (ref "IC4") (pin "7") (pinfunction "VEE_7") (pintype "power_in"))
      (node (ref "IC4") (pin "8") (pinfunction "GND_8") (pintype "power_in"))
      (node (ref "IC5") (pin "1") (pinfunction "GND_1") (pintype "bidirectional"))
      (node (ref "IC5") (pin "21") (pinfunction "BLANK_21") (pintype "bidirectional"))
      (node (ref "IC6") (pin "11") (pinfunction "V-_11") (pintype "power_in"))
      (node (ref "IC6") (pin "12") (pinfunction "+IN_12") (pintype "input"))
      (node (ref "J1") (pin "P1") (pinfunction "1_P1") (pintype "passive"))
      (node (ref "J1") (pin "P2") (pinfunction "2_P2") (pintype "passive"))
      (node (ref "J10") (pin "P1") (pinfunction "1_P1") (pintype "passive"))
      (node (ref "J11") (pin "P1") (pinfunction "1_P1") (pintype "passive"))
      (node (ref "J12") (pin "P1") (pinfunction "1_P1") (pintype "passive"))
      (node (ref "J2") (pin "P1") (pinfunction "1_P1") (pintype "passive"))
      (node (ref "J2") (pin "P2") (pinfunction "2_P2") (pintype "passive"))
      (node (ref "J3") (pin "P1") (pinfunction "1_P1") (pintype "passive"))
      (node (ref "J3") (pin "P2") (pinfunction "2_P2") (pintype "passive"))
      (node (ref "J4") (pin "P1") (pinfunction "1_P1") (pintype "passive"))
      (node (ref "J4") (pin "P2") (pinfunction "2_P2") (pintype "passive"))
      (node (ref "J5") (pin "P1") (pinfunction "1_P1") (pintype "passive"))
      (node (ref "J5") (pin "P2") (pinfunction "2_P2") (pintype "passive"))
      (node (ref "J6") (pin "P1") (pinfunction "1_P1") (pintype "passive"))
      (node (ref "J6") (pin "P2") (pinfunction "2_P2") (pintype "passive"))
      (node (ref "J7") (pin "P1") (pinfunction "1_P1") (pintype "passive"))
      (node (ref "J8") (pin "P1") (pinfunction "1_P1") (pintype "passive"))
      (node (ref "J9") (pin "P1") (pinfunction "1_P1") (pintype "passive"))
      (node (ref "JP1") (pin "3") (pinfunction "3_3") (pintype "passive"))
      (node (ref "JP1") (pin "4") (pinfunction "4_4") (pintype "passive"))
      (node (ref "JP1") (pin "5") (pinfunction "5_5") (pintype "passive"))
      (node (ref "JP1") (pin "6") (pinfunction "6_6") (pintype "passive"))
      (node (ref "JP1") (pin "7") (pinfunction "7_7") (pintype "passive"))
      (node (ref "JP1") (pin "8") (pinfunction "8_8") (pintype "passive"))
      (node (ref "JP2") (pin "1") (pinfunction "1_1") (pintype "passive"))
      (node (ref "POT_A") (pin "P$3") (pinfunction "A_P$3") (pintype "passive"))
      (node (ref "POT_B") (pin "P$3") (pinfunction "A_P$3") (pintype "passive"))
      (node (ref "POT_C") (pin "P$3") (pinfunction "A_P$3") (pintype "passive"))
      (node (ref "Q1") (pin "2") (pinfunction "LID1_2") (pintype "power_in"))
      (node (ref "Q1") (pin "4") (pinfunction "LID2_4") (pintype "power_in"))
      (node (ref "Q2") (pin "E") (pinfunction "E_E") (pintype "passive"))
      (node (ref "Q3") (pin "E") (pinfunction "E_E") (pintype "passive"))
      (node (ref "Q4") (pin "E") (pinfunction "E_E") (pintype "passive"))
      (node (ref "R20") (pin "1") (pinfunction "1_1") (pintype "passive"))
      (node (ref "R21") (pin "1") (pinfunction "1_1") (pintype "passive"))
      (node (ref "R23") (pin "1") (pinfunction "1_1") (pintype "passive"))
      (node (ref "R45") (pin "2") (pinfunction "2_2") (pintype "passive"))
      (node (ref "R46") (pin "2") (pinfunction "2_2") (pintype "passive"))
      (node (ref "R47") (pin "2") (pinfunction "2_2") (pintype "passive"))
      (node (ref "R48") (pin "2") (pinfunction "2_2") (pintype "passive"))
      (node (ref "R49") (pin "2") (pinfunction "2_2") (pintype "passive"))
      (node (ref "R5") (pin "2") (pinfunction "2_2") (pintype "passive"))
      (node (ref "R50") (pin "2") (pinfunction "2_2") (pintype "passive"))
      (node (ref "SLD_A") (pin "1") (pinfunction "A_1") (pintype "passive"))
      (node (ref "SLD_B") (pin "1") (pinfunction "A_1") (pintype "passive"))
      (node (ref "SLD_C") (pin "1") (pinfunction "A_1") (pintype "passive"))
      (node (ref "SW_A") (pin "1") (pinfunction "1_1") (pintype "passive"))
      (node (ref "SW_A") (pin "2") (pinfunction "2_2") (pintype "passive"))
      (node (ref "SW_B") (pin "1") (pinfunction "1_1") (pintype "passive"))
      (node (ref "SW_B") (pin "2") (pinfunction "2_2") (pintype "passive"))
      (node (ref "SW_C") (pin "1") (pinfunction "1_1") (pintype "passive"))
      (node (ref "SW_C") (pin "2") (pinfunction "2_2") (pintype "passive"))
      (node (ref "U$1") (pin "6") (pinfunction "P$6_6") (pintype "bidirectional"))
      (node (ref "U1") (pin "16") (pinfunction "VSS_2_16") (pintype "power_in"))
      (node (ref "U1") (pin "31") (pinfunction "BOOT0_31") (pintype "input"))
      (node (ref "U1") (pin "32") (pinfunction "VSS_1_32") (pintype "power_in"))
      (node (ref "U2") (pin "10") (pinfunction "+IN_10") (pintype "input"))
      (node (ref "U2") (pin "11") (pinfunction "V-_11") (pintype "power_in"))
      (node (ref "U2") (pin "12") (pinfunction "+IN_12") (pintype "input"))
      (node (ref "U2") (pin "3") (pinfunction "+IN_3") (pintype "input"))
      (node (ref "U2") (pin "5") (pinfunction "+IN_5") (pintype "input"))
      (node (ref "U3") (pin "10") (pinfunction "+IN_10") (pintype "input"))
      (node (ref "U3") (pin "12") (pinfunction "+IN_12") (pintype "input"))
      (node (ref "U3") (pin "3") (pinfunction "+IN_3") (pintype "input"))
      (node (ref "U3") (pin "5") (pinfunction "+IN_5") (pintype "input"))
    )
    (net (code "25") (name "LEDS_SCK") (class "Default")
      (node (ref "IC5") (pin "3") (pinfunction "SCLK_3") (pintype "bidirectional"))
      (node (ref "U1") (pin "26") (pinfunction "PB3_26") (pintype "bidirectional"))
    )
    (net (code "26") (name "LEDS_SIN") (class "Default")
      (node (ref "IC5") (pin "2") (pinfunction "SIN_2") (pintype "bidirectional"))
      (node (ref "U1") (pin "28") (pinfunction "PB5_28") (pintype "bidirectional"))
    )
    (net (code "27") (name "LEDS_SS") (class "Default")
      (node (ref "IC5") (pin "4") (pinfunction "LAT_4") (pintype "bidirectional"))
      (node (ref "JP3") (pin "2") (pinfunction "2_2") (pintype "passive"))
    )
    (net (code "28") (name "N_U") (class "Default")
      (node (ref "U2") (pin "6") (pinfunction "-IN_6") (pintype "input"))
      (node (ref "U2") (pin "7") (pinfunction "OUT_7") (pintype "output"))
    )
    (net (code "29") (name "Net-(A-GRN)") (class "Default")
      (node (ref "A") (pin "GREEN_C") (pinfunction "GRN_GREEN_C") (pintype "bidirectional"))
      (node (ref "IC5") (pin "11") (pinfunction "OUT6_11") (pintype "bidirectional"))
    )
    (net (code "30") (name "Net-(A-RED)") (class "Default")
      (node (ref "A") (pin "RED_C") (pinfunction "RED_RED_C") (pintype "bidirectional"))
      (node (ref "IC5") (pin "10") (pinfunction "OUT5_10") (pintype "bidirectional"))
    )
    (net (code "31") (name "Net-(B-GRN)") (class "Default")
      (node (ref "B") (pin "GREEN_C") (pinfunction "GRN_GREEN_C") (pintype "bidirectional"))
      (node (ref "IC5") (pin "9") (pinfunction "OUT4_9") (pintype "bidirectional"))
    )
    (net (code "32") (name "Net-(B-RED)") (class "Default")
      (node (ref "B") (pin "RED_C") (pinfunction "RED_RED_C") (pintype "bidirectional"))
      (node (ref "IC5") (pin "8") (pinfunction "OUT3_8") (pintype "bidirectional"))
    )
    (net (code "33") (name "Net-(C-GRN)") (class "Default")
      (node (ref "C") (pin "GREEN_C") (pinfunction "GRN_GREEN_C") (pintype "bidirectional"))
      (node (ref "IC5") (pin "7") (pinfunction "OUT2_7") (pintype "bidirectional"))
    )
    (net (code "34") (name "Net-(C-RED)") (class "Default")
      (node (ref "C") (pin "RED_C") (pinfunction "RED_RED_C") (pintype "bidirectional"))
      (node (ref "IC5") (pin "6") (pinfunction "OUT1_6") (pintype "bidirectional"))
    )
    (net (code "35") (name "Net-(C1-Pad1)") (class "Default")
      (node (ref "C1") (pin "1") (pinfunction "1_1") (pintype "passive"))
      (node (ref "D1") (pin "C") (pinfunction "C_C") (pintype "passive"))
      (node (ref "L1") (pin "1") (pinfunction "1_1") (pintype "passive"))
      (node (ref "L2") (pin "2") (pinfunction "2_2") (pintype "passive"))
      (node (ref "L3") (pin "2") (pinfunction "2_2") (pintype "passive"))
    )
    (net (code "36") (name "Net-(C3-Pad1)") (class "Default")
      (node (ref "C3") (pin "1") (pinfunction "1_1") (pintype "passive"))
      (node (ref "IC2") (pin "2") (pinfunction "IN_2") (pintype "input"))
      (node (ref "IC2") (pin "4") (pinfunction "IN_4") (pintype "input"))
      (node (ref "L2") (pin "1") (pinfunction "1_1") (pintype "passive"))
    )
    (net (code "37") (name "Net-(C22-Pad2)") (class "Default")
      (node (ref "C22") (pin "2") (pinfunction "2_2") (pintype "passive"))
      (node (ref "Q1") (pin "1") (pinfunction "1_1") (pintype "passive"))
      (node (ref "R6") (pin "2") (pinfunction "2_2") (pintype "passive"))
    )
    (net (code "38") (name "Net-(D2-PadA)") (class "Default")
      (node (ref "D2") (pin "A") (pinfunction "A_A") (pintype "passive"))
      (node (ref "L4") (pin "2") (pinfunction "2_2") (pintype "passive"))
    )
    (net (code "39") (name "Net-(D3-PadC)") (class "Default")
      (node (ref "D3") (pin "C") (pinfunction "C_C") (pintype "passive"))
      (node (ref "Q2") (pin "B") (pinfunction "B_B") (pintype "passive"))
      (node (ref "R18") (pin "2") (pinfunction "2_2") (pintype "passive"))
      (node (ref "R23") (pin "2") (pinfunction "2_2") (pintype "passive"))
    )
    (net (code "40") (name "Net-(D4-PadC)") (class "Default")
      (node (ref "D4") (pin "C") (pinfunction "C_C") (pintype "passive"))
      (node (ref "Q3") (pin "B") (pinfunction "B_B") (pintype "passive"))
      (node (ref "R19") (pin "2") (pinfunction "2_2") (pintype "passive"))
      (node (ref "R20") (pin "2") (pinfunction "2_2") (pintype "passive"))
    )
    (net (code "41") (name "Net-(D5-PadC)") (class "Default")
      (node (ref "D5") (pin "C") (pinfunction "C_C") (pintype "passive"))
      (node (ref "Q4") (pin "B") (pinfunction "B_B") (pintype "passive"))
      (node (ref "R21") (pin "2") (pinfunction "2_2") (pintype "passive"))
      (node (ref "R22") (pin "2") (pinfunction "2_2") (pintype "passive"))
    )
    (net (code "42") (name "Net-(IC1-VI)") (class "Default")
      (node (ref "C5") (pin "1") (pinfunction "1_1") (pintype "passive"))
      (node (ref "IC1") (pin "1") (pinfunction "VI_1") (pintype "input"))
      (node (ref "L1") (pin "2") (pinfunction "2_2") (pintype "passive"))
    )
    (net (code "43") (name "Net-(IC4A-X0)") (class "Default")
      (node (ref "IC4") (pin "13") (pinfunction "X0_13") (pintype "bidirectional"))
      (node (ref "POT_C") (pin "P$2") (pinfunction "S_P$2") (pintype "passive"))
    )
    (net (code "44") (name "Net-(IC4A-X1)") (class "Default")
      (node (ref "IC4") (pin "14") (pinfunction "X1_14") (pintype "bidirectional"))
      (node (ref "SLD_C") (pin "2") (pinfunction "S_2") (pintype "passive"))
    )
    (net (code "45") (name "Net-(IC4A-X2)") (class "Default")
      (node (ref "IC4") (pin "15") (pinfunction "X2_15") (pintype "bidirectional"))
      (node (ref "SLD_B") (pin "2") (pinfunction "S_2") (pintype "passive"))
    )
    (net (code "46") (name "Net-(IC4A-X3)") (class "Default")
      (node (ref "IC4") (pin "12") (pinfunction "X3_12") (pintype "bidirectional"))
      (node (ref "POT_A") (pin "P$2") (pinfunction "S_P$2") (pintype "passive"))
    )
    (net (code "47") (name "Net-(IC4A-X4)") (class "Default")
      (node (ref "IC4") (pin "1") (pinfunction "X4_1") (pintype "bidirectional"))
      (node (ref "SLD_A") (pin "2") (pinfunction "S_2") (pintype "passive"))
    )
    (net (code "48") (name "Net-(IC4A-X5)") (class "Default")
      (node (ref "IC4") (pin "5") (pinfunction "X5_5") (pintype "bidirectional"))
      (node (ref "POT_B") (pin "P$2") (pinfunction "S_P$2") (pintype "passive"))
    )
    (net (code "49") (name "Net-(IC5-IREF)") (class "Default")
      (node (ref "IC5") (pin "23") (pinfunction "IREF_23") (pintype "bidirectional"))
      (node (ref "R5") (pin "1") (pinfunction "1_1") (pintype "passive"))
    )
    (net (code "50") (name "Net-(IC5-OUT7)") (class "Default")
      (node (ref "IC5") (pin "12") (pinfunction "OUT7_12") (pintype "bidirectional"))
      (node (ref "R16") (pin "2") (pinfunction "2_2") (pintype "passive"))
    )
    (net (code "51") (name "Net-(IC5-OUT8)") (class "Default")
      (node (ref "IC5") (pin "13") (pinfunction "OUT8_13") (pintype "bidirectional"))
      (node (ref "R17") (pin "2") (pinfunction "2_2") (pintype "passive"))
    )
    (net (code "52") (name "Net-(IC5-OUT9)") (class "Default")
      (node (ref "IC5") (pin "14") (pinfunction "OUT9_14") (pintype "bidirectional"))
      (node (ref "R15") (pin "2") (pinfunction "2_2") (pintype "passive"))
    )
    (net (code "53") (name "Net-(IC5-VCC)") (class "Default")
      (node (ref "C14") (pin "1") (pinfunction "1_1") (pintype "passive"))
      (node (ref "C15") (pin "1") (pinfunction "1_1") (pintype "passive"))
      (node (ref "IC5") (pin "24") (pinfunction "VCC_24") (pintype "bidirectional"))
      (node (ref "L5") (pin "1") (pinfunction "1_1") (pintype "passive"))
    )
    (net (code "54") (name "Net-(IC6A-+IN)") (class "Default")
      (node (ref "IC6") (pin "3") (pinfunction "+IN_3") (pintype "input"))
      (node (ref "R44") (pin "2") (pinfunction "2_2") (pintype "passive"))
      (node (ref "R47") (pin "1") (pinfunction "1_1") (pintype "passive"))
    )
    (net (code "55") (name "Net-(IC6A--IN)") (class "Default")
      (node (ref "IC6") (pin "2") (pinfunction "-IN_2") (pintype "input"))
      (node (ref "R13") (pin "1") (pinfunction "1_1") (pintype "passive"))
    )
    (net (code "56") (name "Net-(IC6A-OUT)") (class "Default")
      (node (ref "IC6") (pin "1") (pinfunction "OUT_1") (pintype "output"))
      (node (ref "R39") (pin "2") (pinfunction "2_2") (pintype "passive"))
      (node (ref "R44") (pin "1") (pinfunction "1_1") (pintype "passive"))
    )
    (net (code "57") (name "Net-(IC6B-+IN)") (class "Default")
      (node (ref "IC6") (pin "5") (pinfunction "+IN_5") (pintype "input"))
      (node (ref "R41") (pin "2") (pinfunction "2_2") (pintype "passive"))
      (node (ref "R46") (pin "1") (pinfunction "1_1") (pintype "passive"))
    )
    (net (code "58") (name "Net-(IC6B--IN)") (class "Default")
      (node (ref "IC6") (pin "6") (pinfunction "-IN_6") (pintype "input"))
      (node (ref "R12") (pin "1") (pinfunction "1_1") (pintype "passive"))
    )
    (net (code "59") (name "Net-(IC6B-OUT)") (class "Default")
      (node (ref "IC6") (pin "7") (pinfunction "OUT_7") (pintype "output"))
      (node (ref "R38") (pin "2") (pinfunction "2_2") (pintype "passive"))
      (node (ref "R41") (pin "1") (pinfunction "1_1") (pintype "passive"))
    )
    (net (code "60") (name "Net-(IC6C-+IN)") (class "Default")
      (node (ref "IC6") (pin "10") (pinfunction "+IN_10") (pintype "input"))
      (node (ref "R36") (pin "2") (pinfunction "2_2") (pintype "passive"))
      (node (ref "R45") (pin "1") (pinfunction "1_1") (pintype "passive"))
    )
    (net (code "61") (name "Net-(IC6C--IN)") (class "Default")
      (node (ref "IC6") (pin "9") (pinfunction "-IN_9") (pintype "input"))
      (node (ref "R11") (pin "1") (pinfunction "1_1") (pintype "passive"))
    )
    (net (code "62") (name "Net-(IC6C-OUT)") (class "Default")
      (node (ref "IC6") (pin "8") (pinfunction "OUT_8") (pintype "output"))
      (node (ref "R36") (pin "1") (pinfunction "1_1") (pintype "passive"))
      (node (ref "R37") (pin "2") (pinfunction "2_2") (pintype "passive"))
    )
    (net (code "63") (name "Net-(IC6D--IN)") (class "Default")
      (node (ref "IC6") (pin "13") (pinfunction "-IN_13") (pintype "input"))
      (node (ref "IC6") (pin "14") (pinfunction "OUT_14") (pintype "output"))
    )
    (net (code "64") (name "Net-(IC14A-+IN)") (class "Default")
      (node (ref "IC14") (pin "3") (pinfunction "+IN_3") (pintype "input"))
      (node (ref "LED3") (pin "2") (pinfunction "2_2") (pintype "bidirectional"))
      (node (ref "R48") (pin "1") (pinfunction "1_1") (pintype "passive"))
    )
    (net (code "65") (name "Net-(IC14A--IN)") (class "Default")
      (node (ref "C33") (pin "2") (pinfunction "2_2") (pintype "passive"))
      (node (ref "IC14") (pin "2") (pinfunction "-IN_2") (pintype "input"))
      (node (ref "R43") (pin "2") (pinfunction "2_2") (pintype "passive"))
      (node (ref "U3") (pin "1") (pinfunction "OUT_1") (pintype "output"))
    )
    (net (code "66") (name "Net-(IC14A-OUT)") (class "Default")
      (node (ref "IC14") (pin "1") (pinfunction "OUT_1") (pintype "output"))
      (node (ref "LED3") (pin "1") (pinfunction "1_1") (pintype "bidirectional"))
    )
    (net (code "67") (name "Net-(IC14B-+IN)") (class "Default")
      (node (ref "C32") (pin "2") (pinfunction "2_2") (pintype "passive"))
      (node (ref "IC14") (pin "5") (pinfunction "+IN_5") (pintype "input"))
      (node (ref "R42") (pin "2") (pinfunction "2_2") (pintype "passive"))
      (node (ref "U3") (pin "7") (pinfunction "OUT_7") (pintype "output"))
    )
    (net (code "68") (name "Net-(IC14B--IN)") (class "Default")
      (node (ref "IC14") (pin "6") (pinfunction "-IN_6") (pintype "input"))
      (node (ref "LED1") (pin "2") (pinfunction "2_2") (pintype "bidirectional"))
      (node (ref "R49") (pin "1") (pinfunction "1_1") (pintype "passive"))
    )
    (net (code "69") (name "Net-(IC14B-OUT)") (class "Default")
      (node (ref "IC14") (pin "7") (pinfunction "OUT_7") (pintype "output"))
      (node (ref "LED1") (pin "1") (pinfunction "1_1") (pintype "bidirectional"))
    )
    (net (code "70") (name "Net-(IC14C-+IN)") (class "Default")
      (node (ref "IC14") (pin "10") (pinfunction "+IN_10") (pintype "input"))
      (node (ref "LED2") (pin "2") (pinfunction "2_2") (pintype "bidirectional"))
      (node (ref "R50") (pin "1") (pinfunction "1_1") (pintype "passive"))
    )
    (net (code "71") (name "Net-(IC14C--IN)") (class "Default")
      (node (ref "C34") (pin "2") (pinfunction "2_2") (pintype "passive"))
      (node (ref "IC14") (pin "9") (pinfunction "-IN_9") (pintype "input"))
      (node (ref "R40") (pin "2") (pinfunction "2_2") (pintype "passive"))
      (node (ref "U3") (pin "8") (pinfunction "OUT_8") (pintype "output"))
    )
    (net (code "72") (name "Net-(IC14C-OUT)") (class "Default")
      (node (ref "IC14") (pin "8") (pinfunction "OUT_8") (pintype "output"))
      (node (ref "LED2") (pin "1") (pinfunction "1_1") (pintype "bidirectional"))
    )
    (net (code "73") (name "Net-(IC14D-+IN)") (class "Default")
      (node (ref "IC14") (pin "12") (pinfunction "+IN_12") (pintype "input"))
      (node (ref "IC14") (pin "14") (pinfunction "OUT_14") (pintype "output"))
    )
    (net (code "74") (name "Net-(J4-3)") (class "Default")
      (node (ref "J4") (pin "P3") (pinfunction "3_P3") (pintype "passive"))
      (node (ref "R24") (pin "2") (pinfunction "2_2") (pintype "passive"))
    )
    (net (code "75") (name "Net-(J6-3)") (class "Default")
      (node (ref "J6") (pin "P3") (pinfunction "3_P3") (pintype "passive"))
      (node (ref "R26") (pin "2") (pinfunction "2_2") (pintype "passive"))
    )
    (net (code "76") (name "Net-(J7-3)") (class "Default")
      (node (ref "J7") (pin "P3") (pinfunction "3_P3") (pintype "passive"))
      (node (ref "R37") (pin "1") (pinfunction "1_1") (pintype "passive"))
    )
    (net (code "77") (name "Net-(J8-3)") (class "Default")
      (node (ref "J8") (pin "P3") (pinfunction "3_P3") (pintype "passive"))
      (node (ref "R38") (pin "1") (pinfunction "1_1") (pintype "passive"))
    )
    (net (code "78") (name "Net-(J9-3)") (class "Default")
      (node (ref "J9") (pin "P3") (pinfunction "3_P3") (pintype "passive"))
      (node (ref "R39") (pin "1") (pinfunction "1_1") (pintype "passive"))
    )
    (net (code "79") (name "Net-(J10-3)") (class "Default")
      (node (ref "J10") (pin "P3") (pinfunction "3_P3") (pintype "passive"))
      (node (ref "R35") (pin "1") (pinfunction "1_1") (pintype "passive"))
      (node (ref "R40") (pin "1") (pinfunction "1_1") (pintype "passive"))
    )
    (net (code "80") (name "Net-(J11-3)") (class "Default")
      (node (ref "J11") (pin "P3") (pinfunction "3_P3") (pintype "passive"))
      (node (ref "R29") (pin "1") (pinfunction "1_1") (pintype "passive"))
      (node (ref "R42") (pin "1") (pinfunction "1_1") (pintype "passive"))
    )
    (net (code "81") (name "Net-(J12-3)") (class "Default")
      (node (ref "J12") (pin "P3") (pinfunction "3_P3") (pintype "passive"))
      (node (ref "R32") (pin "1") (pinfunction "1_1") (pintype "passive"))
      (node (ref "R43") (pin "1") (pinfunction "1_1") (pintype "passive"))
    )
    (net (code "82") (name "Net-(Q1B-2)") (class "Default")
      (node (ref "C21") (pin "2") (pinfunction "2_2") (pintype "passive"))
      (node (ref "Q1") (pin "3") (pinfunction "2_3") (pintype "passive"))
      (node (ref "R9") (pin "2") (pinfunction "2_2") (pintype "passive"))
    )
    (net (code "83") (name "Net-(SLD_AA-A)") (class "Default")
      (node (ref "SLD_A") (pin "B") (pinfunction "A_B") (pintype "passive"))
      (node (ref "SLD_B") (pin "B") (pinfunction "A_B") (pintype "passive"))
      (node (ref "SLD_C") (pin "B") (pinfunction "A_B") (pintype "passive"))
    )
    (net (code "84") (name "Net-(SLD_AA-C)") (class "Default")
      (node (ref "R16") (pin "1") (pinfunction "1_1") (pintype "passive"))
      (node (ref "SLD_A") (pin "E") (pinfunction "C_E") (pintype "passive"))
    )
    (net (code "85") (name "Net-(SLD_BA-C)") (class "Default")
      (node (ref "R17") (pin "1") (pinfunction "1_1") (pintype "passive"))
      (node (ref "SLD_B") (pin "E") (pinfunction "C_E") (pintype "passive"))
    )
    (net (code "86") (name "Net-(SLD_CA-C)") (class "Default")
      (node (ref "R15") (pin "1") (pinfunction "1_1") (pintype "passive"))
      (node (ref "SLD_C") (pin "E") (pinfunction "C_E") (pintype "passive"))
    )
    (net (code "87") (name "Net-(U1-PF0{slash}OSC_IN)") (class "Default")
      (node (ref "R9") (pin "1") (pinfunction "1_1") (pintype "passive"))
      (node (ref "U1") (pin "2") (pinfunction "PF0/OSC_IN_2") (pintype "bidirectional"))
    )
    (net (code "88") (name "Net-(U1-PF1{slash}OSC_OUT)") (class "Default")
      (node (ref "R6") (pin "1") (pinfunction "1_1") (pintype "passive"))
      (node (ref "U1") (pin "3") (pinfunction "PF1/OSC_OUT_3") (pintype "bidirectional"))
    )
    (net (code "89") (name "Net-(U2A--IN)") (class "Default")
      (node (ref "C30") (pin "1") (pinfunction "1_1") (pintype "passive"))
      (node (ref "R14") (pin "2") (pinfunction "2_2") (pintype "passive"))
      (node (ref "R2") (pin "1") (pinfunction "1_1") (pintype "passive"))
      (node (ref "R26") (pin "1") (pinfunction "1_1") (pintype "passive"))
      (node (ref "U2") (pin "2") (pinfunction "-IN_2") (pintype "input"))
    )
    (net (code "90") (name "Net-(U2C--IN)") (class "Default")
      (node (ref "C23") (pin "1") (pinfunction "1_1") (pintype "passive"))
      (node (ref "R25") (pin "1") (pinfunction "1_1") (pintype "passive"))
      (node (ref "R3") (pin "1") (pinfunction "1_1") (pintype "passive"))
      (node (ref "R7") (pin "2") (pinfunction "2_2") (pintype "passive"))
      (node (ref "U2") (pin "9") (pinfunction "-IN_9") (pintype "input"))
    )
    (net (code "91") (name "Net-(U2D--IN)") (class "Default")
      (node (ref "C24") (pin "1") (pinfunction "1_1") (pintype "passive"))
      (node (ref "R24") (pin "1") (pinfunction "1_1") (pintype "passive"))
      (node (ref "R4") (pin "1") (pinfunction "1_1") (pintype "passive"))
      (node (ref "R8") (pin "2") (pinfunction "2_2") (pintype "passive"))
      (node (ref "U2") (pin "13") (pinfunction "-IN_13") (pintype "input"))
    )
    (net (code "92") (name "Net-(U3A--IN)") (class "Default")
      (node (ref "C33") (pin "1") (pinfunction "1_1") (pintype "passive"))
      (node (ref "R30") (pin "1") (pinfunction "1_1") (pintype "passive"))
      (node (ref "R31") (pin "1") (pinfunction "1_1") (pintype "passive"))
      (node (ref "R32") (pin "2") (pinfunction "2_2") (pintype "passive"))
      (node (ref "U3") (pin "2") (pinfunction "-IN_2") (pintype "input"))
    )
    (net (code "93") (name "Net-(U3B--IN)") (class "Default")
      (node (ref "C32") (pin "1") (pinfunction "1_1") (pintype "passive"))
      (node (ref "R27") (pin "1") (pinfunction "1_1") (pintype "passive"))
      (node (ref "R28") (pin "1") (pinfunction "1_1") (pintype "passive"))
      (node (ref "R29") (pin "2") (pinfunction "2_2") (pintype "passive"))
      (node (ref "U3") (pin "6") (pinfunction "-IN_6") (pintype "input"))
    )
    (net (code "94") (name "Net-(U3C--IN)") (class "Default")
      (node (ref "C34") (pin "1") (pinfunction "1_1") (pintype "passive"))
      (node (ref "R33") (pin "1") (pinfunction "1_1") (pintype "passive"))
      (node (ref "R34") (pin "1") (pinfunction "1_1") (pintype "passive"))
      (node (ref "R35") (pin "2") (pinfunction "2_2") (pintype "passive"))
      (node (ref "U3") (pin "9") (pinfunction "-IN_9") (pintype "input"))
    )
    (net (code "95") (name "Net-(U3D--IN)") (class "Default")
      (node (ref "U3") (pin "13") (pinfunction "-IN_13") (pintype "input"))
      (node (ref "U3") (pin "14") (pinfunction "OUT_14") (pintype "output"))
    )
    (net (code "96") (name "POTS_ADDR_A") (class "Default")
      (node (ref "IC4") (pin "11") (pinfunction "A_11") (pintype "input"))
      (node (ref "U1") (pin "13") (pinfunction "PA7_13") (pintype "bidirectional"))
    )
    (net (code "97") (name "POTS_ADDR_B") (class "Default")
      (node (ref "IC4") (pin "10") (pinfunction "B_10") (pintype "input"))
      (node (ref "U1") (pin "18") (pinfunction "PA8_18") (pintype "bidirectional"))
    )
    (net (code "98") (name "POTS_ADDR_C") (class "Default")
      (node (ref "IC4") (pin "9") (pinfunction "C_9") (pintype "input"))
      (node (ref "U1") (pin "19") (pinfunction "PA9_19") (pintype "bidirectional"))
    )
    (net (code "99") (name "RESET") (class "Default")
      (node (ref "C28") (pin "1") (pinfunction "1_1") (pintype "passive"))
      (node (ref "JP2") (pin "4") (pinfunction "4_4") (pintype "passive"))
      (node (ref "R10") (pin "2") (pinfunction "2_2") (pintype "passive"))
      (node (ref "U1") (pin "4") (pinfunction "NRST_4") (pintype "bidirectional"))
    )
    (net (code "100") (name "SWCLK") (class "Default")
      (node (ref "JP2") (pin "3") (pinfunction "3_3") (pintype "passive"))
      (node (ref "U1") (pin "24") (pinfunction "PA14_24") (pintype "bidirectional"))
    )
    (net (code "101") (name "SWDIO_SS") (class "Default")
      (node (ref "JP2") (pin "2") (pinfunction "2_2") (pintype "passive"))
      (node (ref "JP3") (pin "1") (pinfunction "1_1") (pintype "passive"))
      (node (ref "U1") (pin "23") (pinfunction "PA13_23") (pintype "bidirectional"))
    )
    (net (code "102") (name "SW_MODE_A") (class "Default")
      (node (ref "SW_A") (pin "3") (pinfunction "3_3") (pintype "passive"))
      (node (ref "SW_A") (pin "4") (pinfunction "4_4") (pintype "passive"))
      (node (ref "U1") (pin "27") (pinfunction "PB4_27") (pintype "bidirectional"))
    )
    (net (code "103") (name "SW_MODE_B") (class "Default")
      (node (ref "SW_B") (pin "3") (pinfunction "3_3") (pintype "passive"))
      (node (ref "SW_B") (pin "4") (pinfunction "4_4") (pintype "passive"))
      (node (ref "U1") (pin "29") (pinfunction "PB6_29") (pintype "bidirectional"))
    )
    (net (code "104") (name "SW_MODE_C") (class "Default")
      (node (ref "SW_C") (pin "3") (pinfunction "3_3") (pintype "passive"))
      (node (ref "SW_C") (pin "4") (pinfunction "4_4") (pintype "passive"))
      (node (ref "U1") (pin "30") (pinfunction "PB7_30") (pintype "bidirectional"))
    )
    (net (code "105") (name "VCC") (class "Default")
      (node (ref "C2") (pin "1") (pinfunction "1_1") (pintype "passive"))
      (node (ref "C31") (pin "1") (pinfunction "1_1") (pintype "passive"))
      (node (ref "C35") (pin "1") (pinfunction "1_1") (pintype "passive"))
      (node (ref "C36") (pin "1") (pinfunction "1_1") (pintype "passive"))
      (node (ref "C4") (pin "1") (pinfunction "1_1") (pintype "passive"))
      (node (ref "IC14") (pin "4") (pinfunction "V+_4") (pintype "power_in"))
      (node (ref "IC6") (pin "4") (pinfunction "V+_4") (pintype "power_in"))
      (node (ref "L3") (pin "1") (pinfunction "1_1") (pintype "passive"))
      (node (ref "U$1") (pin "1") (pinfunction "P$1_1") (pintype "bidirectional"))
      (node (ref "U3") (pin "4") (pinfunction "V+_4") (pintype "power_in"))
    )
    (net (code "106") (name "VEE") (class "Default")
      (node (ref "C10") (pin "2") (pinfunction "2_2") (pintype "passive"))
      (node (ref "C25") (pin "2") (pinfunction "2_2") (pintype "passive"))
      (node (ref "C37") (pin "2") (pinfunction "2_2") (pintype "passive"))
      (node (ref "C9") (pin "2") (pinfunction "2_2") (pintype "passive"))
      (node (ref "IC14") (pin "11") (pinfunction "V-_11") (pintype "power_in"))
      (node (ref "L4") (pin "1") (pinfunction "1_1") (pintype "passive"))
      (node (ref "R1") (pin "1") (pinfunction "1_1") (pintype "passive"))
      (node (ref "U$1") (pin "2") (pinfunction "P$2_2") (pintype "bidirectional"))
      (node (ref "U3") (pin "11") (pinfunction "V-_11") (pintype "power_in"))
    )
    (net (code "107") (name "unconnected-(IC4A-X7-Pad4)") (class "Default")
      (node (ref "IC4") (pin "4") (pinfunction "X7_4") (pintype "bidirectional"))
    )
    (net (code "108") (name "unconnected-(IC5-OUT0-Pad5)") (class "Default")
      (node (ref "IC5") (pin "5") (pinfunction "OUT0_5") (pintype "bidirectional"))
    )
    (net (code "109") (name "unconnected-(IC5-OUT10-Pad15)") (class "Default")
      (node (ref "IC5") (pin "15") (pinfunction "OUT10_15") (pintype "bidirectional"))
    )
    (net (code "110") (name "unconnected-(IC5-OUT11-Pad16)") (class "Default")
      (node (ref "IC5") (pin "16") (pinfunction "OUT11_16") (pintype "bidirectional"))
    )
    (net (code "111") (name "unconnected-(IC5-OUT12-Pad17)") (class "Default")
      (node (ref "IC5") (pin "17") (pinfunction "OUT12_17") (pintype "bidirectional"))
    )
    (net (code "112") (name "unconnected-(IC5-OUT13-Pad18)") (class "Default")
      (node (ref "IC5") (pin "18") (pinfunction "OUT13_18") (pintype "bidirectional"))
    )
    (net (code "113") (name "unconnected-(IC5-OUT14-Pad19)") (class "Default")
      (node (ref "IC5") (pin "19") (pinfunction "OUT14_19") (pintype "bidirectional"))
    )
    (net (code "114") (name "unconnected-(IC5-OUT15-Pad20)") (class "Default")
      (node (ref "IC5") (pin "20") (pinfunction "OUT15_20") (pintype "bidirectional"))
    )
    (net (code "115") (name "unconnected-(IC5-SOUT-Pad22)") (class "Default")
      (node (ref "IC5") (pin "22") (pinfunction "SOUT_22") (pintype "bidirectional"))
    )
    (net (code "116") (name "unconnected-(J7-2-PadP2)") (class "Default")
      (node (ref "J7") (pin "P2") (pinfunction "2_P2") (pintype "passive"))
    )
    (net (code "117") (name "unconnected-(J8-2-PadP2)") (class "Default")
      (node (ref "J8") (pin "P2") (pinfunction "2_P2") (pintype "passive"))
    )
    (net (code "118") (name "unconnected-(J9-2-PadP2)") (class "Default")
      (node (ref "J9") (pin "P2") (pinfunction "2_P2") (pintype "passive"))
    )
    (net (code "119") (name "unconnected-(J10-2-PadP2)") (class "Default")
      (node (ref "J10") (pin "P2") (pinfunction "2_P2") (pintype "passive"))
    )
    (net (code "120") (name "unconnected-(J11-2-PadP2)") (class "Default")
      (node (ref "J11") (pin "P2") (pinfunction "2_P2") (pintype "passive"))
    )
    (net (code "121") (name "unconnected-(J12-2-PadP2)") (class "Default")
      (node (ref "J12") (pin "P2") (pinfunction "2_P2") (pintype "passive"))
    )
  )
)
